# harp_behavior_v2_0.net
KiCad netlist of a schematic drawn in EAGLE
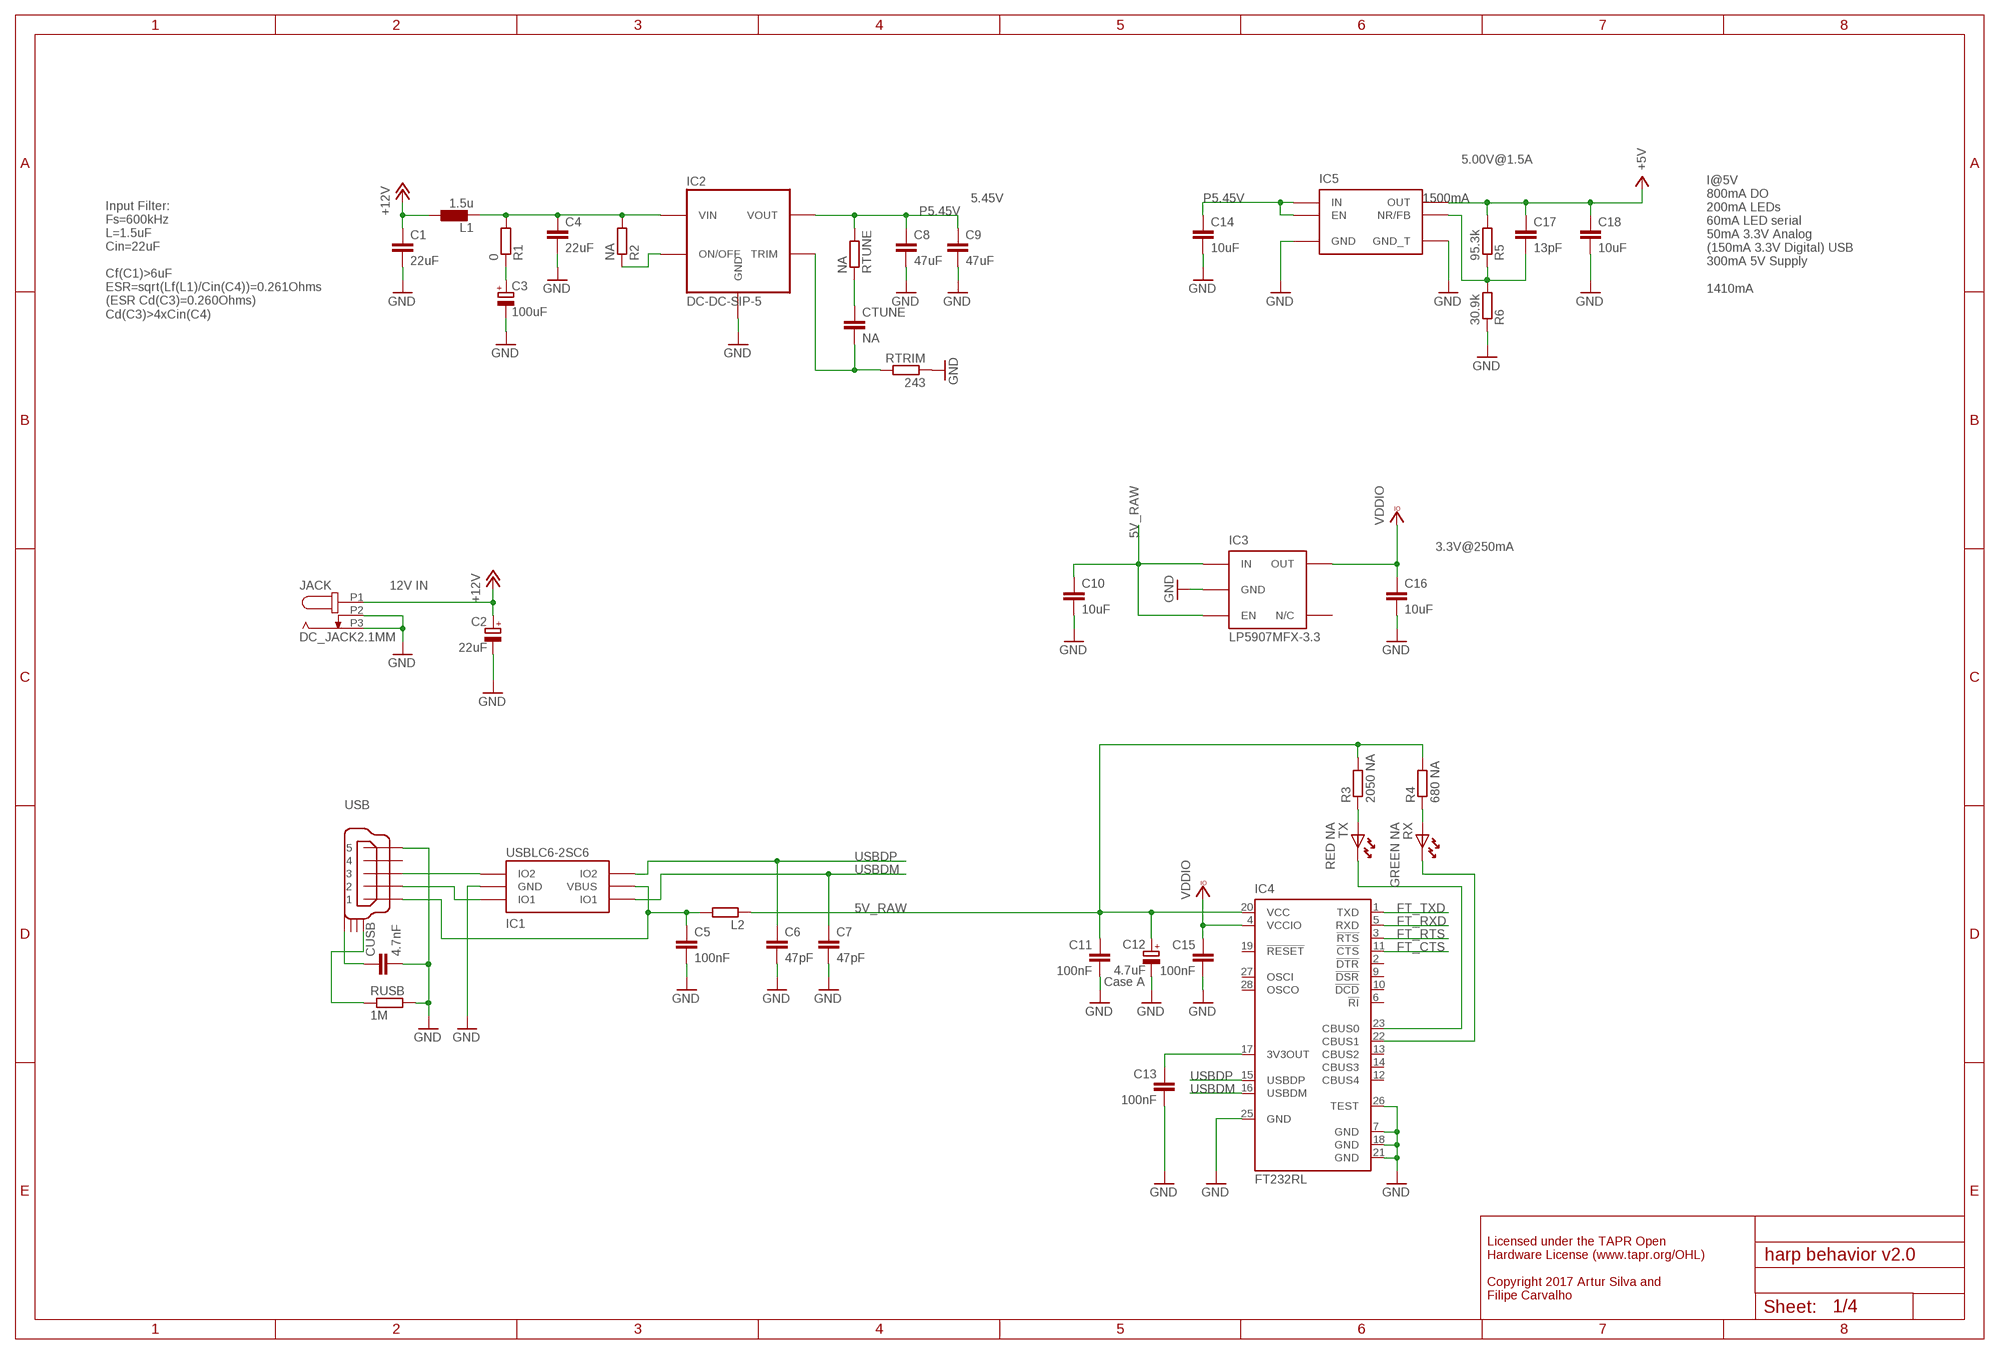
[diagram p0: schematic, sheet 1]
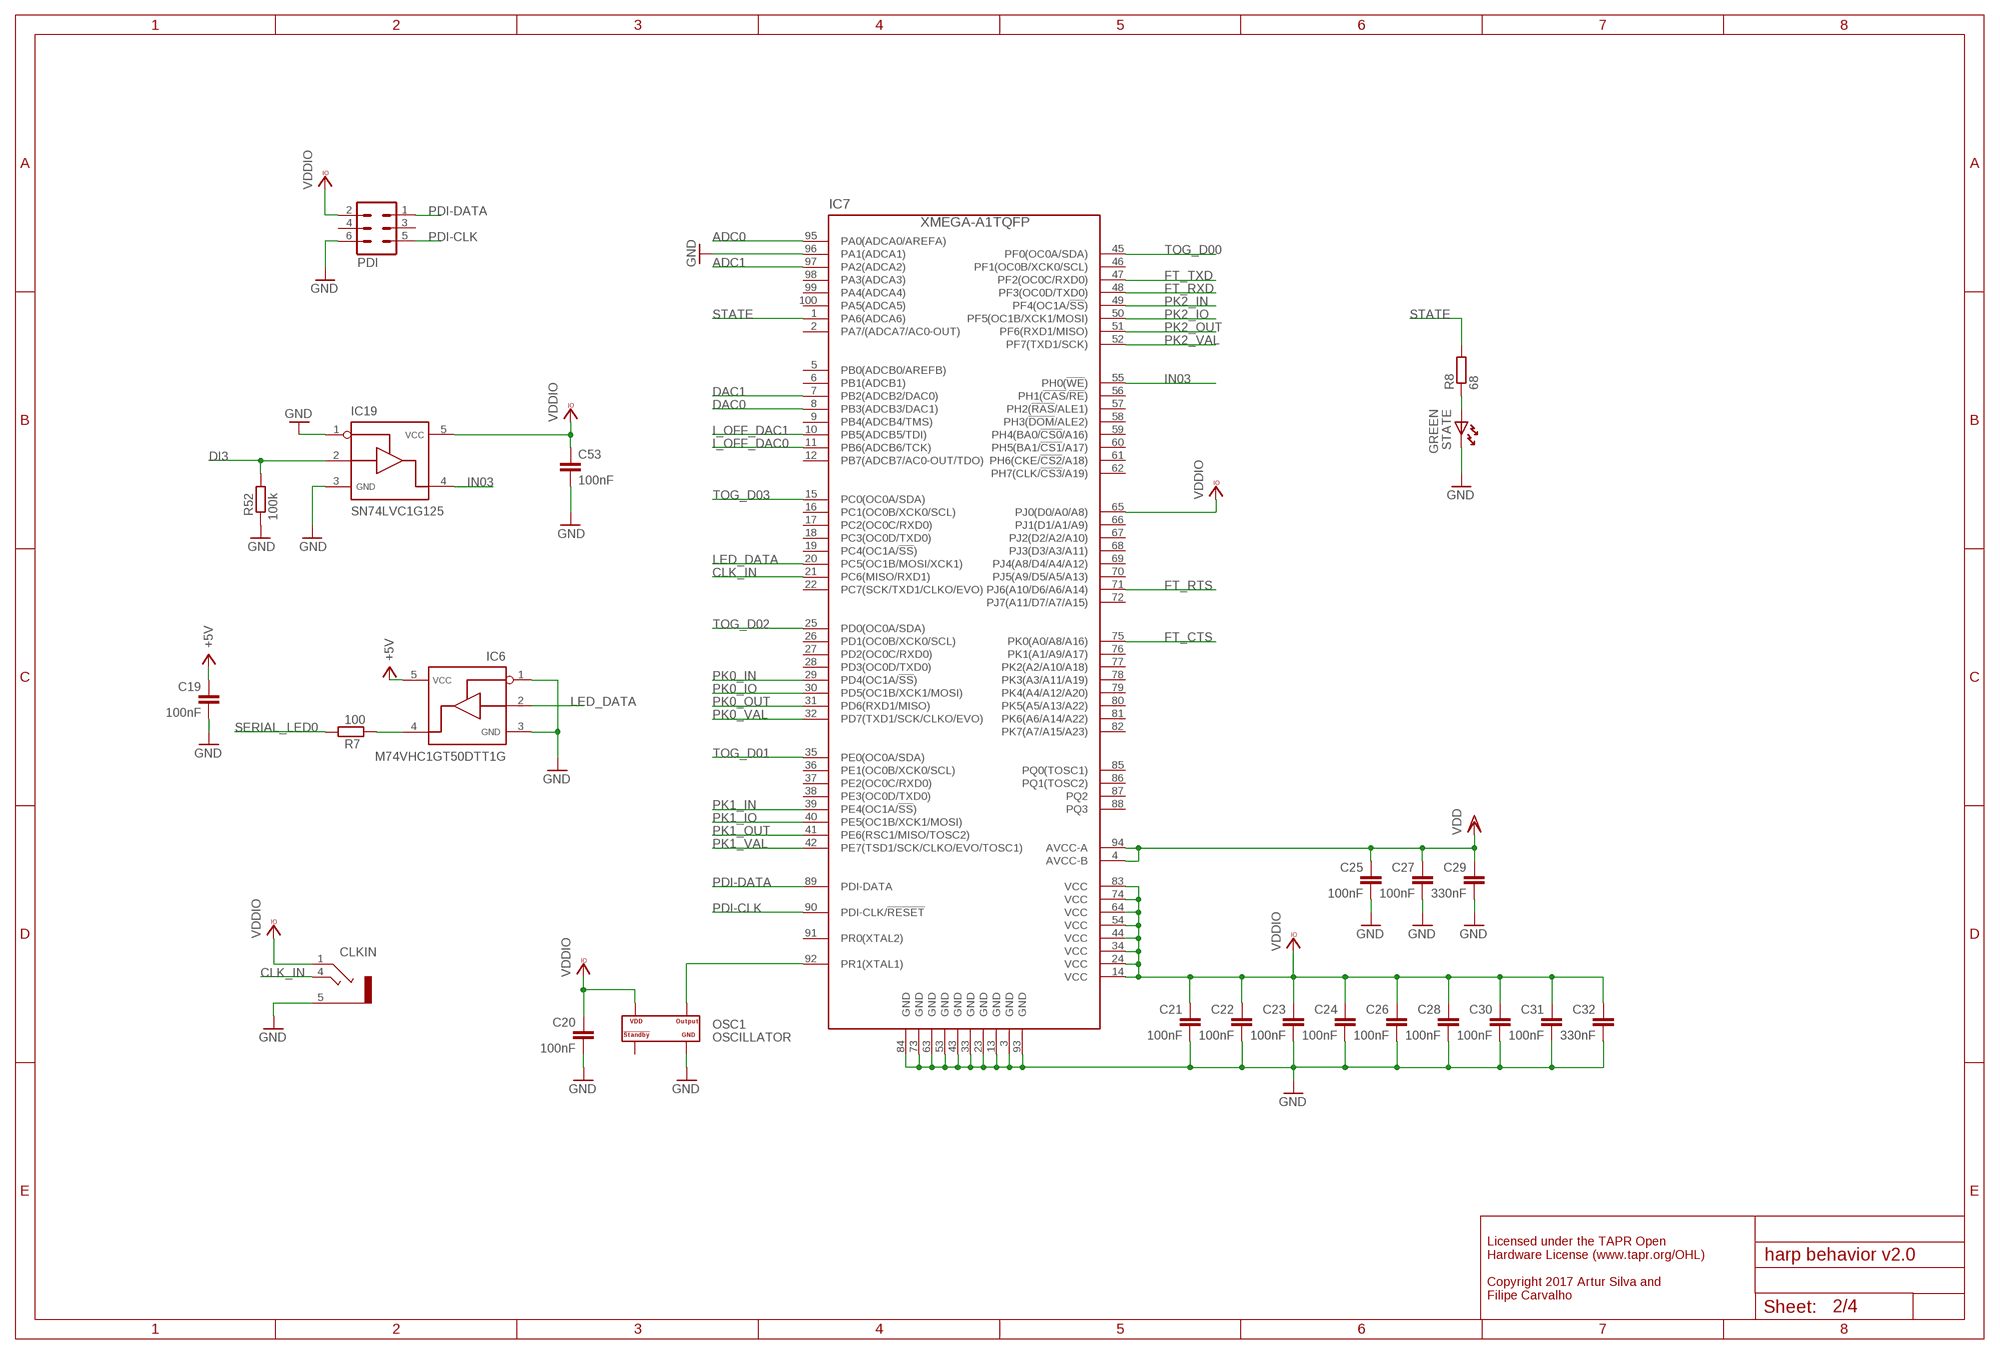
[diagram p1: schematic, sheet 2]
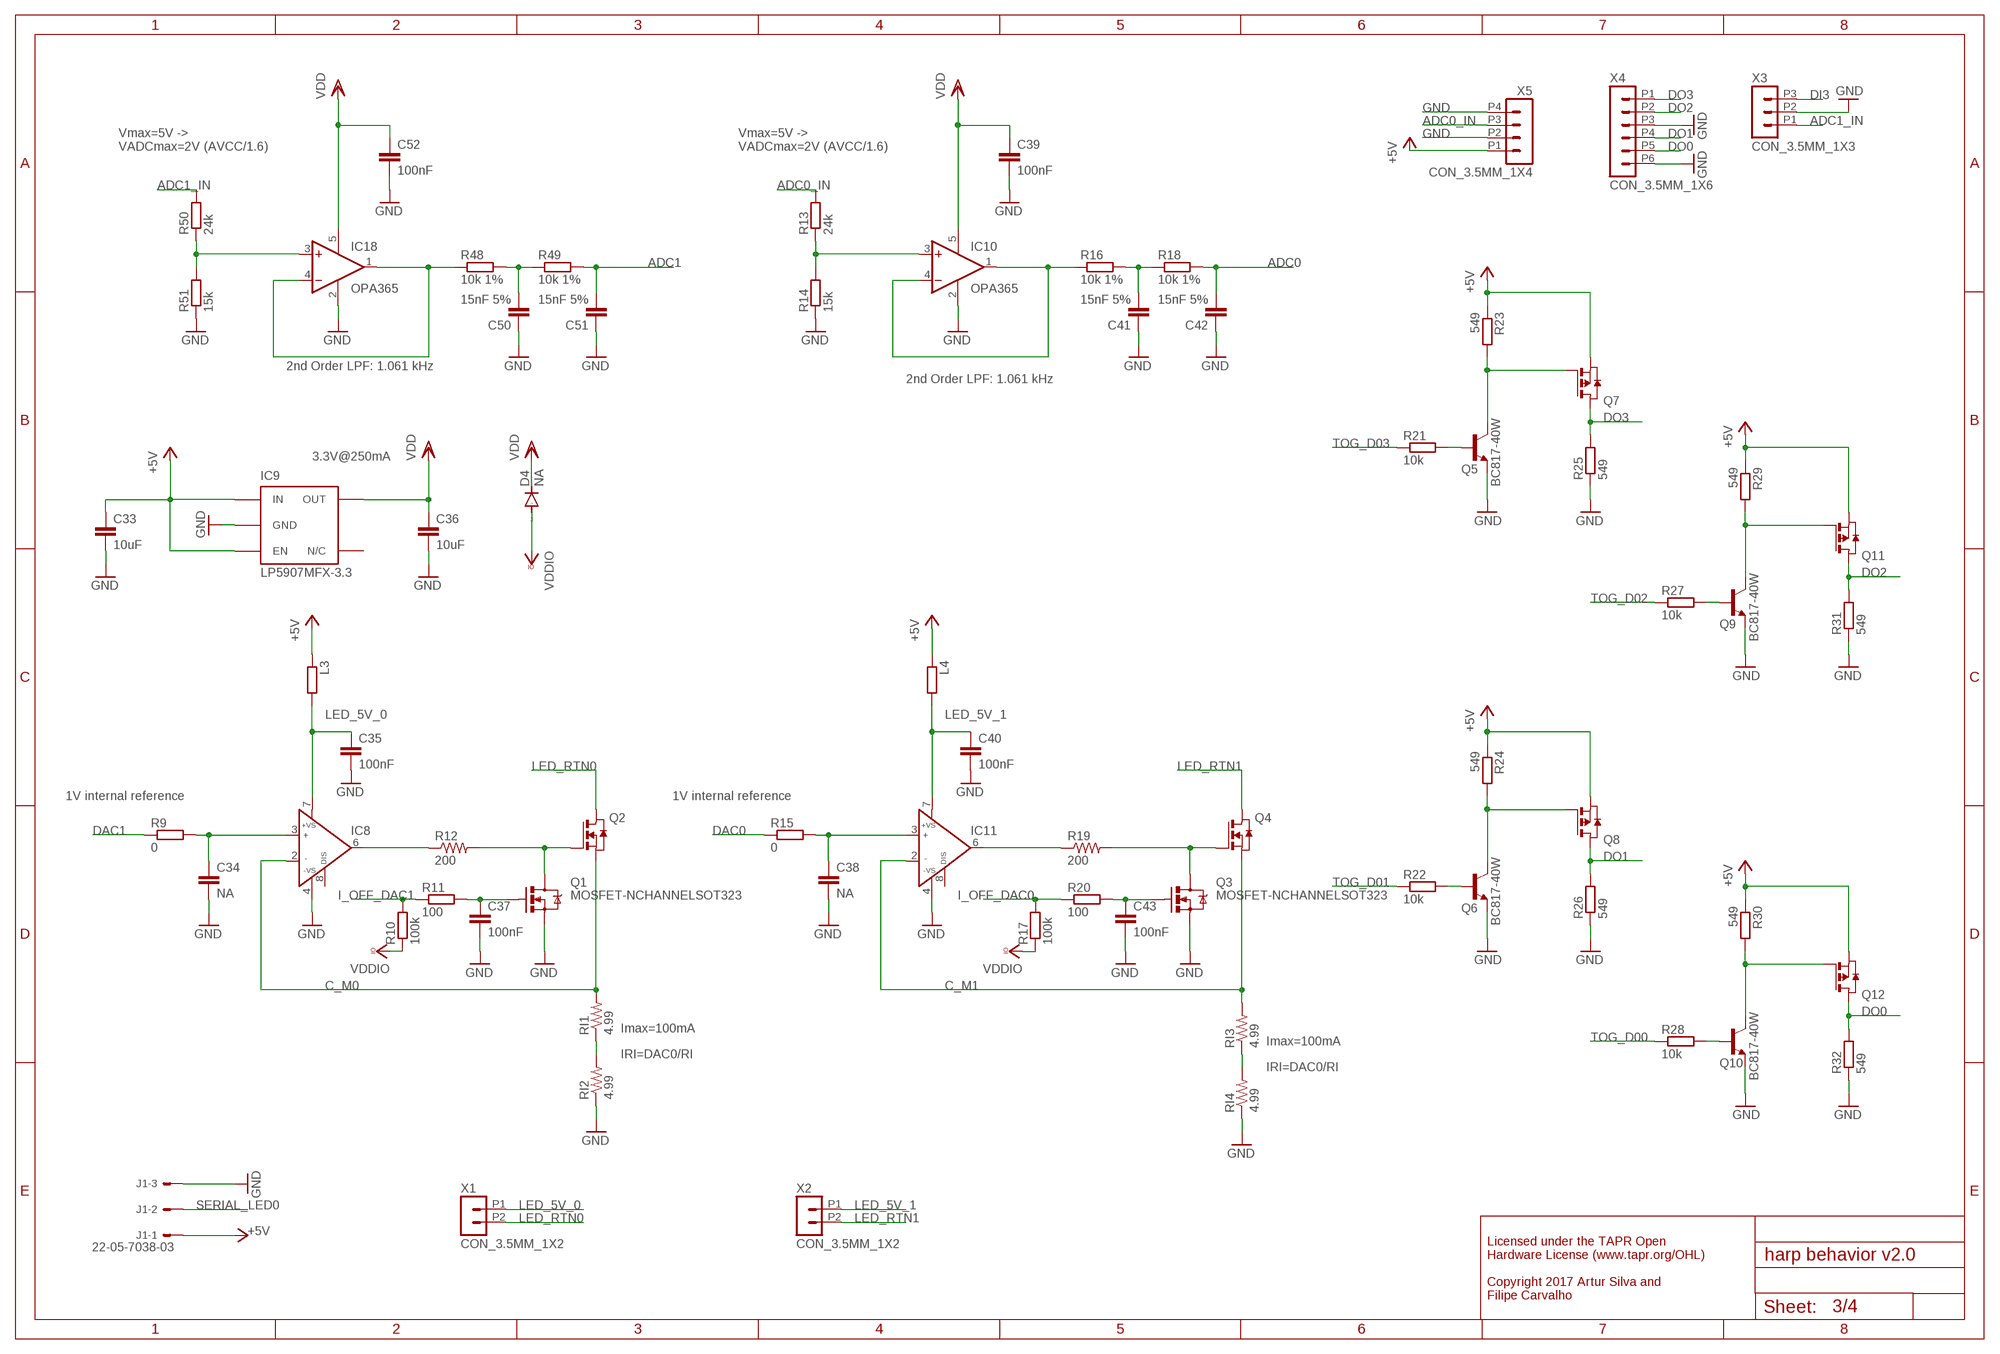
[diagram p2: schematic, sheet 3]
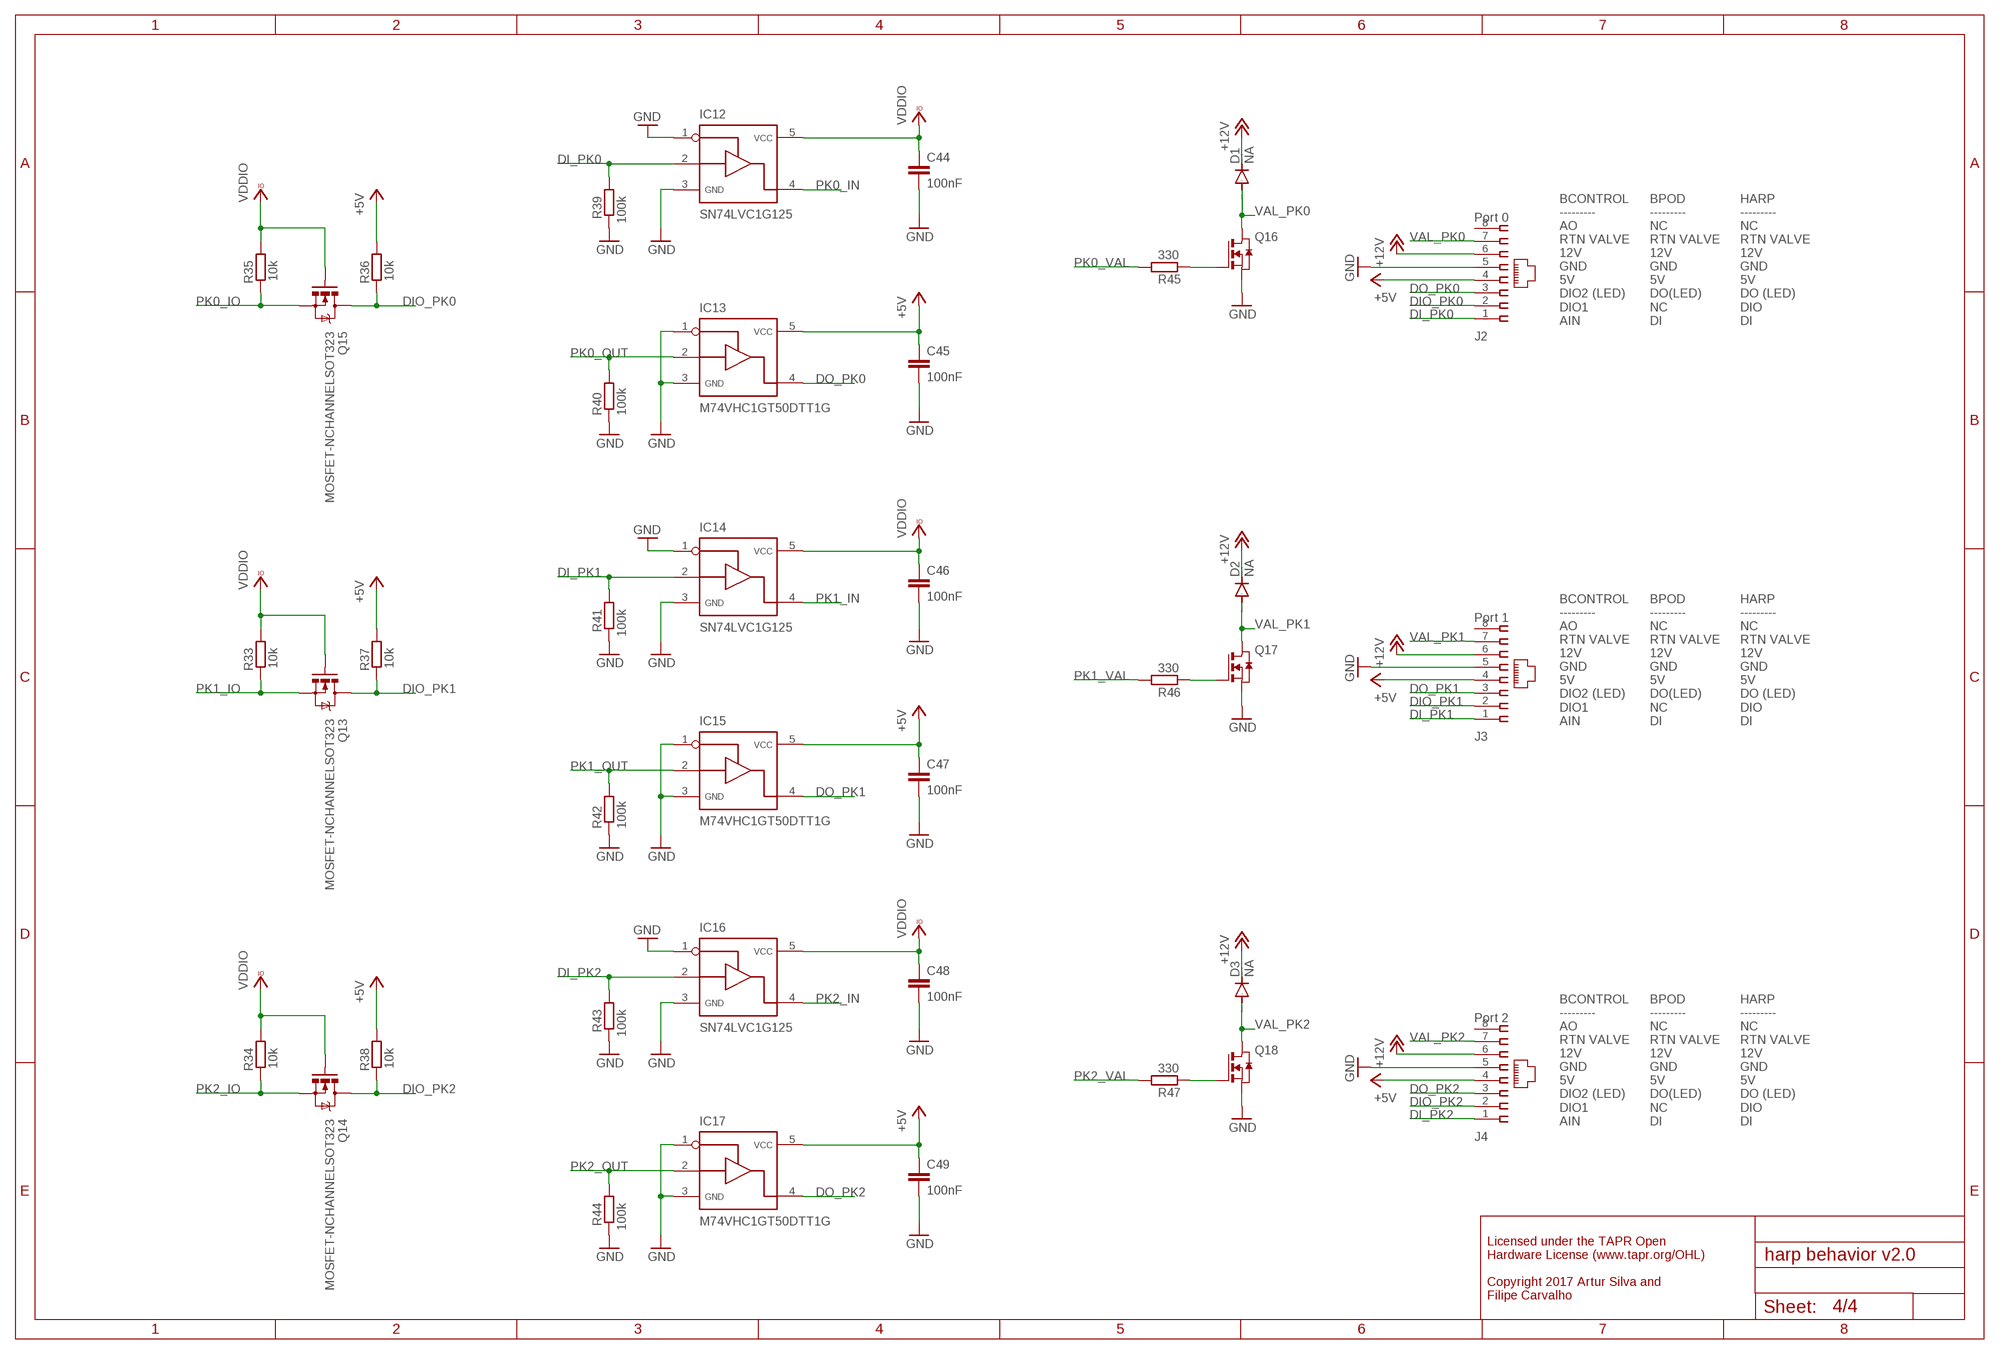
[diagram p3: schematic, sheet 4]

(export (version "E")
  (design (tool "Eeschema 10.0.6"))
  (components
    (comp (ref "C1")
      (value "22uF")
      (footprint "eagle-import:C1210")
      (libsource (lib "eagle-import") (part "C-EUC1210"))
    )
    (comp (ref "C2")
      (value "22uF")
      (footprint "eagle-import:CAP_100UF_HAND")
      (libsource (lib "eagle-import") (part "CAP_100UFHAND"))
    )
    (comp (ref "C3")
      (value "100uF")
      (footprint "eagle-import:PANASONIC_E")
      (libsource (lib "eagle-import") (part "CPOL-EUE"))
    )
    (comp (ref "C4")
      (value "22uF")
      (footprint "eagle-import:C1210")
      (libsource (lib "eagle-import") (part "C-EUC1210"))
    )
    (comp (ref "C5")
      (value "100nF")
      (footprint "eagle-import:C0402")
      (libsource (lib "eagle-import") (part "C-EUC0402"))
    )
    (comp (ref "C6")
      (value "47pF")
      (footprint "eagle-import:C0402")
      (libsource (lib "eagle-import") (part "C-EUC0402"))
    )
    (comp (ref "C7")
      (value "47pF")
      (footprint "eagle-import:C0402")
      (libsource (lib "eagle-import") (part "C-EUC0402"))
    )
    (comp (ref "C8")
      (value "47uF")
      (footprint "eagle-import:C1210")
      (libsource (lib "eagle-import") (part "C-EUC1210"))
    )
    (comp (ref "C9")
      (value "47uF")
      (footprint "eagle-import:C1210")
      (libsource (lib "eagle-import") (part "C-EUC1210"))
    )
    (comp (ref "C10")
      (value "10uF")
      (footprint "eagle-import:C0603")
      (libsource (lib "eagle-import") (part "C-EUC0603"))
    )
    (comp (ref "C11")
      (value "100nF")
      (footprint "eagle-import:C0402")
      (libsource (lib "eagle-import") (part "C-EUC0402"))
    )
    (comp (ref "C12")
      (value "4.7uF")
      (footprint "eagle-import:A_3216-18W")
      (libsource (lib "eagle-import") (part "CPOL-EUA/3216-18W"))
    )
    (comp (ref "C13")
      (value "100nF")
      (footprint "eagle-import:C0402")
      (libsource (lib "eagle-import") (part "C-EUC0402"))
    )
    (comp (ref "C14")
      (value "10uF")
      (footprint "eagle-import:C0603")
      (libsource (lib "eagle-import") (part "C-EUC0603"))
    )
    (comp (ref "C15")
      (value "100nF")
      (footprint "eagle-import:C0402")
      (libsource (lib "eagle-import") (part "C-EUC0402"))
    )
    (comp (ref "C16")
      (value "10uF")
      (footprint "eagle-import:C0603")
      (libsource (lib "eagle-import") (part "C-EUC0603"))
    )
    (comp (ref "C17")
      (value "13pF")
      (footprint "eagle-import:C0402")
      (libsource (lib "eagle-import") (part "C-EUC0402"))
    )
    (comp (ref "C18")
      (value "10uF")
      (footprint "eagle-import:C0603")
      (libsource (lib "eagle-import") (part "C-EUC0603"))
    )
    (comp (ref "CTUNE")
      (value "NA")
      (footprint "eagle-import:C0402")
      (libsource (lib "eagle-import") (part "C-EUC0402"))
    )
    (comp (ref "CUSB")
      (value "4.7nF")
      (footprint "eagle-import:C0402")
      (libsource (lib "eagle-import") (part "C-EUC0402"))
    )
    (comp (ref "IC1")
      (value "USBLC6-2SC6")
      (footprint "eagle-import:SOT23-6L")
      (libsource (lib "eagle-import") (part "USBLC6-2"))
    )
    (comp (ref "IC2")
      (value "DC-DC-SIP-5")
      (footprint "eagle-import:SIP-5")
      (libsource (lib "eagle-import") (part "DC-DC-SIP-5"))
    )
    (comp (ref "IC3")
      (value "LP5907MFX-3.3")
      (footprint "eagle-import:TSOT23-5")
      (libsource (lib "eagle-import") (part "TLV700XX"))
    )
    (comp (ref "IC4")
      (value "FT232RL")
      (footprint "eagle-import:SSOP28")
      (libsource (lib "eagle-import") (part "FT232RL"))
    )
    (comp (ref "IC5")
      (value "TPS78601SON")
      (footprint "eagle-import:SON-8")
      (libsource (lib "eagle-import") (part "TPS78601SON"))
    )
    (comp (ref "JACK")
      (value "DC_JACK2.1MM")
      (footprint "eagle-import:DC_POWER_INPUT_2.1MM")
      (libsource (lib "eagle-import") (part "DC_JACK2.1MM"))
    )
    (comp (ref "L1")
      (value "1.5u")
      (footprint "eagle-import:IND_LPS4012_V2")
      (libsource (lib "eagle-import") (part "INDLPS4012_L"))
    )
    (comp (ref "L2")
      (value "???")
      (footprint "eagle-import:R0805")
      (libsource (lib "eagle-import") (part "R-EU_R0805"))
    )
    (comp (ref "R1")
      (value "0")
      (footprint "eagle-import:R0402")
      (libsource (lib "eagle-import") (part "R-EU_R0402"))
    )
    (comp (ref "R2")
      (value "NA")
      (footprint "eagle-import:R0402")
      (libsource (lib "eagle-import") (part "R-EU_R0402"))
    )
    (comp (ref "R3")
      (value "2050 NA")
      (footprint "eagle-import:R0402")
      (libsource (lib "eagle-import") (part "R-EU_R0402"))
    )
    (comp (ref "R4")
      (value "680 NA")
      (footprint "eagle-import:R0402")
      (libsource (lib "eagle-import") (part "R-EU_R0402"))
    )
    (comp (ref "R5")
      (value "95.3k")
      (footprint "eagle-import:R0402")
      (libsource (lib "eagle-import") (part "R-EU_R0402"))
    )
    (comp (ref "R6")
      (value "30.9k")
      (footprint "eagle-import:R0402")
      (libsource (lib "eagle-import") (part "R-EU_R0402"))
    )
    (comp (ref "RTRIM")
      (value "243")
      (footprint "eagle-import:R0402")
      (libsource (lib "eagle-import") (part "R-EU_R0402"))
    )
    (comp (ref "RTUNE")
      (value "NA")
      (footprint "eagle-import:R0402")
      (libsource (lib "eagle-import") (part "R-EU_R0402"))
    )
    (comp (ref "RUSB")
      (value "1M")
      (footprint "eagle-import:R0402")
      (libsource (lib "eagle-import") (part "R-EU_R0402"))
    )
    (comp (ref "RX")
      (value "GREEN NA")
      (footprint "eagle-import:LED_HAND")
      (libsource (lib "eagle-import") (part "LEDHAND"))
    )
    (comp (ref "TX")
      (value "RED NA")
      (footprint "eagle-import:LED_HAND")
      (libsource (lib "eagle-import") (part "LEDHAND"))
    )
    (comp (ref "USB")
      (value "USB_MINI_B")
      (footprint "eagle-import:240-0002-1")
      (libsource (lib "eagle-import") (part "USB_MINI_B"))
    )
    (comp (ref "C44")
      (value "100nF")
      (footprint "eagle-import:C0402")
      (libsource (lib "eagle-import") (part "C-EUC0402"))
    )
    (comp (ref "C45")
      (value "100nF")
      (footprint "eagle-import:C0402")
      (libsource (lib "eagle-import") (part "C-EUC0402"))
    )
    (comp (ref "C46")
      (value "100nF")
      (footprint "eagle-import:C0402")
      (libsource (lib "eagle-import") (part "C-EUC0402"))
    )
    (comp (ref "C47")
      (value "100nF")
      (footprint "eagle-import:C0402")
      (libsource (lib "eagle-import") (part "C-EUC0402"))
    )
    (comp (ref "C48")
      (value "100nF")
      (footprint "eagle-import:C0402")
      (libsource (lib "eagle-import") (part "C-EUC0402"))
    )
    (comp (ref "C49")
      (value "100nF")
      (footprint "eagle-import:C0402")
      (libsource (lib "eagle-import") (part "C-EUC0402"))
    )
    (comp (ref "D1")
      (value "NA")
      (footprint "eagle-import:SOD-323-DIODE")
      (libsource (lib "eagle-import") (part "DIODE"))
    )
    (comp (ref "D2")
      (value "NA")
      (footprint "eagle-import:SOD-323-DIODE")
      (libsource (lib "eagle-import") (part "DIODE"))
    )
    (comp (ref "D3")
      (value "NA")
      (footprint "eagle-import:SOD-323-DIODE")
      (libsource (lib "eagle-import") (part "DIODE"))
    )
    (comp (ref "IC12")
      (value "SN74LVC1G125")
      (footprint "eagle-import:SOT23-5")
      (libsource (lib "eagle-import") (part "SN74LVC1G125"))
    )
    (comp (ref "IC13")
      (value "M74VHC1GT50DTT1G")
      (footprint "eagle-import:SOT23-5")
      (libsource (lib "eagle-import") (part "SN74LVC1G125"))
    )
    (comp (ref "IC14")
      (value "SN74LVC1G125")
      (footprint "eagle-import:SOT23-5")
      (libsource (lib "eagle-import") (part "SN74LVC1G125"))
    )
    (comp (ref "IC15")
      (value "M74VHC1GT50DTT1G")
      (footprint "eagle-import:SOT23-5")
      (libsource (lib "eagle-import") (part "SN74LVC1G125"))
    )
    (comp (ref "IC16")
      (value "SN74LVC1G125")
      (footprint "eagle-import:SOT23-5")
      (libsource (lib "eagle-import") (part "SN74LVC1G125"))
    )
    (comp (ref "IC17")
      (value "M74VHC1GT50DTT1G")
      (footprint "eagle-import:SOT23-5")
      (libsource (lib "eagle-import") (part "SN74LVC1G125"))
    )
    (comp (ref "J2")
      (value "Port 0")
      (footprint "eagle-import:520426-4")
      (libsource (lib "eagle-import") (part "520426-4"))
    )
    (comp (ref "J3")
      (value "Port 1")
      (footprint "eagle-import:520426-4")
      (libsource (lib "eagle-import") (part "520426-4"))
    )
    (comp (ref "J4")
      (value "Port 2")
      (footprint "eagle-import:520426-4")
      (libsource (lib "eagle-import") (part "520426-4"))
    )
    (comp (ref "Q13")
      (value "MOSFET-NCHANNELSOT323")
      (footprint "eagle-import:SOT323")
      (libsource (lib "eagle-import") (part "MOSFET-NCHANNELSOT323"))
    )
    (comp (ref "Q14")
      (value "MOSFET-NCHANNELSOT323")
      (footprint "eagle-import:SOT323")
      (libsource (lib "eagle-import") (part "MOSFET-NCHANNELSOT323"))
    )
    (comp (ref "Q15")
      (value "MOSFET-NCHANNELSOT323")
      (footprint "eagle-import:SOT323")
      (libsource (lib "eagle-import") (part "MOSFET-NCHANNELSOT323"))
    )
    (comp (ref "Q16")
      (value "NMOSSOT223")
      (footprint "eagle-import:SOT223")
      (libsource (lib "eagle-import") (part "NMOSSOT223"))
    )
    (comp (ref "Q17")
      (value "NMOSSOT223")
      (footprint "eagle-import:SOT223")
      (libsource (lib "eagle-import") (part "NMOSSOT223"))
    )
    (comp (ref "Q18")
      (value "NMOSSOT223")
      (footprint "eagle-import:SOT223")
      (libsource (lib "eagle-import") (part "NMOSSOT223"))
    )
    (comp (ref "R33")
      (value "10k")
      (footprint "eagle-import:R0402")
      (libsource (lib "eagle-import") (part "R-EU_R0402"))
    )
    (comp (ref "R34")
      (value "10k")
      (footprint "eagle-import:R0402")
      (libsource (lib "eagle-import") (part "R-EU_R0402"))
    )
    (comp (ref "R35")
      (value "10k")
      (footprint "eagle-import:R0402")
      (libsource (lib "eagle-import") (part "R-EU_R0402"))
    )
    (comp (ref "R36")
      (value "10k")
      (footprint "eagle-import:R0402")
      (libsource (lib "eagle-import") (part "R-EU_R0402"))
    )
    (comp (ref "R37")
      (value "10k")
      (footprint "eagle-import:R0402")
      (libsource (lib "eagle-import") (part "R-EU_R0402"))
    )
    (comp (ref "R38")
      (value "10k")
      (footprint "eagle-import:R0402")
      (libsource (lib "eagle-import") (part "R-EU_R0402"))
    )
    (comp (ref "R39")
      (value "100k")
      (footprint "eagle-import:R0402")
      (libsource (lib "eagle-import") (part "R-EU_R0402"))
    )
    (comp (ref "R40")
      (value "100k")
      (footprint "eagle-import:R0402")
      (libsource (lib "eagle-import") (part "R-EU_R0402"))
    )
    (comp (ref "R41")
      (value "100k")
      (footprint "eagle-import:R0402")
      (libsource (lib "eagle-import") (part "R-EU_R0402"))
    )
    (comp (ref "R42")
      (value "100k")
      (footprint "eagle-import:R0402")
      (libsource (lib "eagle-import") (part "R-EU_R0402"))
    )
    (comp (ref "R43")
      (value "100k")
      (footprint "eagle-import:R0402")
      (libsource (lib "eagle-import") (part "R-EU_R0402"))
    )
    (comp (ref "R44")
      (value "100k")
      (footprint "eagle-import:R0402")
      (libsource (lib "eagle-import") (part "R-EU_R0402"))
    )
    (comp (ref "R45")
      (value "330")
      (footprint "eagle-import:R0402")
      (libsource (lib "eagle-import") (part "R-EU_R0402"))
    )
    (comp (ref "R46")
      (value "330")
      (footprint "eagle-import:R0402")
      (libsource (lib "eagle-import") (part "R-EU_R0402"))
    )
    (comp (ref "R47")
      (value "330")
      (footprint "eagle-import:R0402")
      (libsource (lib "eagle-import") (part "R-EU_R0402"))
    )
    (comp (ref "C19")
      (value "100nF")
      (footprint "eagle-import:C0402")
      (libsource (lib "eagle-import") (part "C-EUC0402"))
    )
    (comp (ref "C20")
      (value "100nF")
      (footprint "eagle-import:C0402")
      (libsource (lib "eagle-import") (part "C-EUC0402"))
    )
    (comp (ref "C21")
      (value "100nF")
      (footprint "eagle-import:C0402")
      (libsource (lib "eagle-import") (part "C-EUC0402"))
    )
    (comp (ref "C22")
      (value "100nF")
      (footprint "eagle-import:C0402")
      (libsource (lib "eagle-import") (part "C-EUC0402"))
    )
    (comp (ref "C23")
      (value "100nF")
      (footprint "eagle-import:C0402")
      (libsource (lib "eagle-import") (part "C-EUC0402"))
    )
    (comp (ref "C24")
      (value "100nF")
      (footprint "eagle-import:C0402")
      (libsource (lib "eagle-import") (part "C-EUC0402"))
    )
    (comp (ref "C25")
      (value "100nF")
      (footprint "eagle-import:C0402")
      (libsource (lib "eagle-import") (part "C-EUC0402"))
    )
    (comp (ref "C26")
      (value "100nF")
      (footprint "eagle-import:C0402")
      (libsource (lib "eagle-import") (part "C-EUC0402"))
    )
    (comp (ref "C27")
      (value "100nF")
      (footprint "eagle-import:C0402")
      (libsource (lib "eagle-import") (part "C-EUC0402"))
    )
    (comp (ref "C28")
      (value "100nF")
      (footprint "eagle-import:C0402")
      (libsource (lib "eagle-import") (part "C-EUC0402"))
    )
    (comp (ref "C29")
      (value "330nF")
      (footprint "eagle-import:C0402")
      (libsource (lib "eagle-import") (part "C-EUC0402"))
    )
    (comp (ref "C30")
      (value "100nF")
      (footprint "eagle-import:C0402")
      (libsource (lib "eagle-import") (part "C-EUC0402"))
    )
    (comp (ref "C31")
      (value "100nF")
      (footprint "eagle-import:C0402")
      (libsource (lib "eagle-import") (part "C-EUC0402"))
    )
    (comp (ref "C32")
      (value "330nF")
      (footprint "eagle-import:C0402")
      (libsource (lib "eagle-import") (part "C-EUC0402"))
    )
    (comp (ref "C53")
      (value "100nF")
      (footprint "eagle-import:C0402")
      (libsource (lib "eagle-import") (part "C-EUC0402"))
    )
    (comp (ref "CLKIN")
      (value "STEREO_JACK")
      (footprint "eagle-import:35RASMT2BHNTRX")
      (libsource (lib "eagle-import") (part "STEREO_JACK"))
    )
    (comp (ref "IC6")
      (value "M74VHC1GT50DTT1G")
      (footprint "eagle-import:SOT23-5")
      (libsource (lib "eagle-import") (part "SN74LVC1G125"))
    )
    (comp (ref "IC7")
      (value "XMEGA-A1TQFP")
      (footprint "eagle-import:TQFP100")
      (libsource (lib "eagle-import") (part "XMEGA-A1TQFP"))
    )
    (comp (ref "IC19")
      (value "SN74LVC1G125")
      (footprint "eagle-import:SOT23-5")
      (libsource (lib "eagle-import") (part "SN74LVC1G125"))
    )
    (comp (ref "OSC1")
      (value "OSCILLATOR")
      (footprint "eagle-import:OSCILLATOR_3.2X2.5")
      (libsource (lib "eagle-import") (part "OSCILLATOR"))
    )
    (comp (ref "PDI")
      (value "MA03-2")
      (footprint "eagle-import:MA03-2")
      (libsource (lib "eagle-import") (part "MA03-2"))
    )
    (comp (ref "R7")
      (value "100")
      (footprint "eagle-import:R0402")
      (libsource (lib "eagle-import") (part "R-EU_R0402"))
    )
    (comp (ref "R8")
      (value "68")
      (footprint "eagle-import:R0402")
      (libsource (lib "eagle-import") (part "R-EU_R0402"))
    )
    (comp (ref "R52")
      (value "100k")
      (footprint "eagle-import:R0402")
      (libsource (lib "eagle-import") (part "R-EU_R0402"))
    )
    (comp (ref "STATE")
      (value "GREEN")
      (footprint "eagle-import:LED_HAND")
      (libsource (lib "eagle-import") (part "LEDHAND"))
    )
    (comp (ref "C33")
      (value "10uF")
      (footprint "eagle-import:C0603")
      (libsource (lib "eagle-import") (part "C-EUC0603"))
    )
    (comp (ref "C34")
      (value "NA")
      (footprint "eagle-import:C0402")
      (libsource (lib "eagle-import") (part "C-EUC0402"))
    )
    (comp (ref "C35")
      (value "100nF")
      (footprint "eagle-import:C0402")
      (libsource (lib "eagle-import") (part "C-EUC0402"))
    )
    (comp (ref "C36")
      (value "10uF")
      (footprint "eagle-import:C0603")
      (libsource (lib "eagle-import") (part "C-EUC0603"))
    )
    (comp (ref "C37")
      (value "100nF")
      (footprint "eagle-import:C0402")
      (libsource (lib "eagle-import") (part "C-EUC0402"))
    )
    (comp (ref "C38")
      (value "NA")
      (footprint "eagle-import:C0402")
      (libsource (lib "eagle-import") (part "C-EUC0402"))
    )
    (comp (ref "C39")
      (value "100nF")
      (footprint "eagle-import:C0402")
      (libsource (lib "eagle-import") (part "C-EUC0402"))
    )
    (comp (ref "C40")
      (value "100nF")
      (footprint "eagle-import:C0402")
      (libsource (lib "eagle-import") (part "C-EUC0402"))
    )
    (comp (ref "C41")
      (value "15nF 5%")
      (footprint "eagle-import:C0402")
      (libsource (lib "eagle-import") (part "C-EUC0402"))
    )
    (comp (ref "C42")
      (value "15nF 5%")
      (footprint "eagle-import:C0402")
      (libsource (lib "eagle-import") (part "C-EUC0402"))
    )
    (comp (ref "C43")
      (value "100nF")
      (footprint "eagle-import:C0402")
      (libsource (lib "eagle-import") (part "C-EUC0402"))
    )
    (comp (ref "C50")
      (value "15nF 5%")
      (footprint "eagle-import:C0402")
      (libsource (lib "eagle-import") (part "C-EUC0402"))
    )
    (comp (ref "C51")
      (value "15nF 5%")
      (footprint "eagle-import:C0402")
      (libsource (lib "eagle-import") (part "C-EUC0402"))
    )
    (comp (ref "C52")
      (value "100nF")
      (footprint "eagle-import:C0402")
      (libsource (lib "eagle-import") (part "C-EUC0402"))
    )
    (comp (ref "D4")
      (value "NA")
      (footprint "eagle-import:SOD-323-DIODE")
      (libsource (lib "eagle-import") (part "DIODE"))
    )
    (comp (ref "IC8")
      (value "AD8041R")
      (footprint "eagle-import:SO8")
      (fields (field (name "MF") "ALTERA CORPORATION") (field (name "MPN") "AD8041ARZ"))
      (libsource (lib "eagle-import") (part "AD8041R"))
    )
    (comp (ref "IC9")
      (value "LP5907MFX-3.3")
      (footprint "eagle-import:TSOT23-5")
      (libsource (lib "eagle-import") (part "TLV700XX"))
    )
    (comp (ref "IC10")
      (value "OPA365")
      (footprint "eagle-import:SOT23-5")
      (libsource (lib "eagle-import") (part "OPA365"))
    )
    (comp (ref "IC11")
      (value "AD8041R")
      (footprint "eagle-import:SO8")
      (fields (field (name "MF") "ALTERA CORPORATION") (field (name "MPN") "AD8041ARZ"))
      (libsource (lib "eagle-import") (part "AD8041R"))
    )
    (comp (ref "IC18")
      (value "OPA365")
      (footprint "eagle-import:SOT23-5")
      (libsource (lib "eagle-import") (part "OPA365"))
    )
    (comp (ref "J1")
      (value "22-05-7038-03")
      (footprint "eagle-import:7395-03")
      (libsource (lib "eagle-import") (part "22-?-0305-7038"))
    )
    (comp (ref "L3")
      (value "600@100M")
      (footprint "eagle-import:R0805")
      (libsource (lib "eagle-import") (part "R-EU_R0805"))
    )
    (comp (ref "L4")
      (value "600@100M")
      (footprint "eagle-import:R0805")
      (libsource (lib "eagle-import") (part "R-EU_R0805"))
    )
    (comp (ref "Q1")
      (value "MOSFET-NCHANNELSOT323")
      (footprint "eagle-import:SOT323")
      (libsource (lib "eagle-import") (part "MOSFET-NCHANNELSOT323"))
    )
    (comp (ref "Q2")
      (value "NMOSSOT223")
      (footprint "eagle-import:SOT223")
      (libsource (lib "eagle-import") (part "NMOSSOT223"))
    )
    (comp (ref "Q3")
      (value "MOSFET-NCHANNELSOT323")
      (footprint "eagle-import:SOT323")
      (libsource (lib "eagle-import") (part "MOSFET-NCHANNELSOT323"))
    )
    (comp (ref "Q4")
      (value "NMOSSOT223")
      (footprint "eagle-import:SOT223")
      (libsource (lib "eagle-import") (part "NMOSSOT223"))
    )
    (comp (ref "Q5")
      (value "BC817-40W")
      (footprint "eagle-import:SOT323-BEC")
      (libsource (lib "eagle-import") (part "BC817"))
    )
    (comp (ref "Q6")
      (value "BC817-40W")
      (footprint "eagle-import:SOT323-BEC")
      (libsource (lib "eagle-import") (part "BC817"))
    )
    (comp (ref "Q7")
      (value "PMOSSOT223")
      (footprint "eagle-import:SOT223")
      (libsource (lib "eagle-import") (part "PMOSSOT223"))
    )
    (comp (ref "Q8")
      (value "PMOSSOT223")
      (footprint "eagle-import:SOT223")
      (libsource (lib "eagle-import") (part "PMOSSOT223"))
    )
    (comp (ref "Q9")
      (value "BC817-40W")
      (footprint "eagle-import:SOT323-BEC")
      (libsource (lib "eagle-import") (part "BC817"))
    )
    (comp (ref "Q10")
      (value "BC817-40W")
      (footprint "eagle-import:SOT323-BEC")
      (libsource (lib "eagle-import") (part "BC817"))
    )
    (comp (ref "Q11")
      (value "PMOSSOT223")
      (footprint "eagle-import:SOT223")
      (libsource (lib "eagle-import") (part "PMOSSOT223"))
    )
    (comp (ref "Q12")
      (value "PMOSSOT223")
      (footprint "eagle-import:SOT223")
      (libsource (lib "eagle-import") (part "PMOSSOT223"))
    )
    (comp (ref "R9")
      (value "0")
      (footprint "eagle-import:R0402")
      (libsource (lib "eagle-import") (part "R-EU_R0402"))
    )
    (comp (ref "R10")
      (value "100k")
      (footprint "eagle-import:R0402")
      (libsource (lib "eagle-import") (part "R-EU_R0402"))
    )
    (comp (ref "R11")
      (value "100")
      (footprint "eagle-import:R0402")
      (libsource (lib "eagle-import") (part "R-EU_R0402"))
    )
    (comp (ref "R12")
      (value "200")
      (footprint "eagle-import:R1210")
      (libsource (lib "eagle-import") (part "R-US_R1210"))
    )
    (comp (ref "R13")
      (value "24k")
      (footprint "eagle-import:R0402")
      (libsource (lib "eagle-import") (part "R-EU_R0402"))
    )
    (comp (ref "R14")
      (value "15k")
      (footprint "eagle-import:R0402")
      (libsource (lib "eagle-import") (part "R-EU_R0402"))
    )
    (comp (ref "R15")
      (value "0")
      (footprint "eagle-import:R0402")
      (libsource (lib "eagle-import") (part "R-EU_R0402"))
    )
    (comp (ref "R16")
      (value "10k 1%")
      (footprint "eagle-import:R0402")
      (libsource (lib "eagle-import") (part "R-EU_R0402"))
    )
    (comp (ref "R17")
      (value "100k")
      (footprint "eagle-import:R0402")
      (libsource (lib "eagle-import") (part "R-EU_R0402"))
    )
    (comp (ref "R18")
      (value "10k 1%")
      (footprint "eagle-import:R0402")
      (libsource (lib "eagle-import") (part "R-EU_R0402"))
    )
    (comp (ref "R19")
      (value "200")
      (footprint "eagle-import:R1210")
      (libsource (lib "eagle-import") (part "R-US_R1210"))
    )
    (comp (ref "R20")
      (value "100")
      (footprint "eagle-import:R0402")
      (libsource (lib "eagle-import") (part "R-EU_R0402"))
    )
    (comp (ref "R21")
      (value "10k")
      (footprint "eagle-import:R0402")
      (libsource (lib "eagle-import") (part "R-EU_R0402"))
    )
    (comp (ref "R22")
      (value "10k")
      (footprint "eagle-import:R0402")
      (libsource (lib "eagle-import") (part "R-EU_R0402"))
    )
    (comp (ref "R23")
      (value "549")
      (footprint "eagle-import:R0805")
      (libsource (lib "eagle-import") (part "R-EU_R0805"))
    )
    (comp (ref "R24")
      (value "549")
      (footprint "eagle-import:R0805")
      (libsource (lib "eagle-import") (part "R-EU_R0805"))
    )
    (comp (ref "R25")
      (value "549")
      (footprint "eagle-import:R0805")
      (libsource (lib "eagle-import") (part "R-EU_R0805"))
    )
    (comp (ref "R26")
      (value "549")
      (footprint "eagle-import:R0805")
      (libsource (lib "eagle-import") (part "R-EU_R0805"))
    )
    (comp (ref "R27")
      (value "10k")
      (footprint "eagle-import:R0402")
      (libsource (lib "eagle-import") (part "R-EU_R0402"))
    )
    (comp (ref "R28")
      (value "10k")
      (footprint "eagle-import:R0402")
      (libsource (lib "eagle-import") (part "R-EU_R0402"))
    )
    (comp (ref "R29")
      (value "549")
      (footprint "eagle-import:R0805")
      (libsource (lib "eagle-import") (part "R-EU_R0805"))
    )
    (comp (ref "R30")
      (value "549")
      (footprint "eagle-import:R0805")
      (libsource (lib "eagle-import") (part "R-EU_R0805"))
    )
    (comp (ref "R31")
      (value "549")
      (footprint "eagle-import:R0805")
      (libsource (lib "eagle-import") (part "R-EU_R0805"))
    )
    (comp (ref "R32")
      (value "549")
      (footprint "eagle-import:R0805")
      (libsource (lib "eagle-import") (part "R-EU_R0805"))
    )
    (comp (ref "R48")
      (value "10k 1%")
      (footprint "eagle-import:R0402")
      (libsource (lib "eagle-import") (part "R-EU_R0402"))
    )
    (comp (ref "R49")
      (value "10k 1%")
      (footprint "eagle-import:R0402")
      (libsource (lib "eagle-import") (part "R-EU_R0402"))
    )
    (comp (ref "R50")
      (value "24k")
      (footprint "eagle-import:R0402")
      (libsource (lib "eagle-import") (part "R-EU_R0402"))
    )
    (comp (ref "R51")
      (value "15k")
      (footprint "eagle-import:R0402")
      (libsource (lib "eagle-import") (part "R-EU_R0402"))
    )
    (comp (ref "RI1")
      (value "4.99")
      (footprint "eagle-import:R2512")
      (libsource (lib "eagle-import") (part "R-US_R2512"))
    )
    (comp (ref "RI2")
      (value "4.99")
      (footprint "eagle-import:R2512")
      (libsource (lib "eagle-import") (part "R-US_R2512"))
    )
    (comp (ref "RI3")
      (value "4.99")
      (footprint "eagle-import:R2512")
      (libsource (lib "eagle-import") (part "R-US_R2512"))
    )
    (comp (ref "RI4")
      (value "4.99")
      (footprint "eagle-import:R2512")
      (libsource (lib "eagle-import") (part "R-US_R2512"))
    )
    (comp (ref "X1")
      (value "CON_3.5MM_1X2")
      (footprint "eagle-import:CON_3.5MM_1X2")
      (libsource (lib "eagle-import") (part "CON_3.5MM_1X2"))
    )
    (comp (ref "X2")
      (value "CON_3.5MM_1X2")
      (footprint "eagle-import:CON_3.5MM_1X2")
      (libsource (lib "eagle-import") (part "CON_3.5MM_1X2"))
    )
    (comp (ref "X3")
      (value "CON_3.5MM_1X3")
      (footprint "eagle-import:CON_3.5MM_1X3")
      (libsource (lib "eagle-import") (part "CON_3.5MM_1X3"))
    )
    (comp (ref "X4")
      (value "CON_3.5MM_1X6")
      (footprint "eagle-import:CON_3.5MM_1X6")
      (libsource (lib "eagle-import") (part "CON_3.5MM_1X6"))
    )
    (comp (ref "X5")
      (value "CON_3.5MM_1X4")
      (footprint "eagle-import:CON_3.5MM_1X4")
      (libsource (lib "eagle-import") (part "CON_3.5MM_1X4"))
    )
  )
  (nets
    (net (code "1") (name "+5V") (class "Default")
      (node (ref "C17") (pin "1") (pinfunction "1_1") (pintype "passive"))
      (node (ref "C18") (pin "1") (pinfunction "1_1") (pintype "passive"))
      (node (ref "C19") (pin "1") (pinfunction "1_1") (pintype "passive"))
      (node (ref "C33") (pin "1") (pinfunction "1_1") (pintype "passive"))
      (node (ref "C45") (pin "1") (pinfunction "1_1") (pintype "passive"))
      (node (ref "C47") (pin "1") (pinfunction "1_1") (pintype "passive"))
      (node (ref "C49") (pin "1") (pinfunction "1_1") (pintype "passive"))
      (node (ref "IC13") (pin "5") (pinfunction "P$5_5") (pintype "bidirectional"))
      (node (ref "IC15") (pin "5") (pinfunction "P$5_5") (pintype "bidirectional"))
      (node (ref "IC17") (pin "5") (pinfunction "P$5_5") (pintype "bidirectional"))
      (node (ref "IC5") (pin "P3") (pinfunction "OUT_P3") (pintype "bidirectional"))
      (node (ref "IC5") (pin "P4") (pinfunction "OUT_P4") (pintype "bidirectional"))
      (node (ref "IC6") (pin "5") (pinfunction "P$5_5") (pintype "bidirectional"))
      (node (ref "IC9") (pin "1") (pinfunction "IN_1") (pintype "bidirectional"))
      (node (ref "IC9") (pin "3") (pinfunction "EN_3") (pintype "bidirectional"))
      (node (ref "J1") (pin "1") (pinfunction "S_1") (pintype "passive"))
      (node (ref "J2") (pin "4") (pinfunction "4_4") (pintype "passive"))
      (node (ref "J3") (pin "4") (pinfunction "4_4") (pintype "passive"))
      (node (ref "J4") (pin "4") (pinfunction "4_4") (pintype "passive"))
      (node (ref "L3") (pin "1") (pinfunction "1_1") (pintype "passive"))
      (node (ref "L4") (pin "1") (pinfunction "1_1") (pintype "passive"))
      (node (ref "Q11") (pin "3") (pinfunction "S_3") (pintype "passive"))
      (node (ref "Q12") (pin "3") (pinfunction "S_3") (pintype "passive"))
      (node (ref "Q7") (pin "3") (pinfunction "S_3") (pintype "passive"))
      (node (ref "Q8") (pin "3") (pinfunction "S_3") (pintype "passive"))
      (node (ref "R23") (pin "1") (pinfunction "1_1") (pintype "passive"))
      (node (ref "R24") (pin "1") (pinfunction "1_1") (pintype "passive"))
      (node (ref "R29") (pin "1") (pinfunction "1_1") (pintype "passive"))
      (node (ref "R30") (pin "1") (pinfunction "1_1") (pintype "passive"))
      (node (ref "R36") (pin "1") (pinfunction "1_1") (pintype "passive"))
      (node (ref "R37") (pin "1") (pinfunction "1_1") (pintype "passive"))
      (node (ref "R38") (pin "1") (pinfunction "1_1") (pintype "passive"))
      (node (ref "R5") (pin "2") (pinfunction "2_2") (pintype "passive"))
      (node (ref "X5") (pin "P1") (pinfunction "1_P1") (pintype "passive"))
    )
    (net (code "2") (name "+12V") (class "Default")
      (node (ref "C1") (pin "1") (pinfunction "1_1") (pintype "passive"))
      (node (ref "C2") (pin "+") (pinfunction "+_+") (pintype "passive"))
      (node (ref "D1") (pin "C") (pinfunction "C_C") (pintype "passive"))
      (node (ref "D2") (pin "C") (pinfunction "C_C") (pintype "passive"))
      (node (ref "D3") (pin "C") (pinfunction "C_C") (pintype "passive"))
      (node (ref "J2") (pin "6") (pinfunction "6_6") (pintype "passive"))
      (node (ref "J3") (pin "6") (pinfunction "6_6") (pintype "passive"))
      (node (ref "J4") (pin "6") (pinfunction "6_6") (pintype "passive"))
      (node (ref "JACK") (pin "P1") (pinfunction "1_P1") (pintype "passive"))
      (node (ref "L1") (pin "1") (pinfunction "1_1") (pintype "passive"))
    )
    (net (code "3") (name "5V_RAW") (class "Default")
      (node (ref "C10") (pin "1") (pinfunction "1_1") (pintype "passive"))
      (node (ref "C11") (pin "1") (pinfunction "1_1") (pintype "passive"))
      (node (ref "C12") (pin "+") (pinfunction "+_+") (pintype "passive"))
      (node (ref "IC3") (pin "1") (pinfunction "IN_1") (pintype "bidirectional"))
      (node (ref "IC3") (pin "3") (pinfunction "EN_3") (pintype "bidirectional"))
      (node (ref "IC4") (pin "20") (pinfunction "VCC_20") (pintype "power_in"))
      (node (ref "L2") (pin "1") (pinfunction "1_1") (pintype "passive"))
      (node (ref "R3") (pin "2") (pinfunction "2_2") (pintype "passive"))
      (node (ref "R4") (pin "2") (pinfunction "2_2") (pintype "passive"))
    )
    (net (code "4") (name "ADC0") (class "Default")
      (node (ref "C42") (pin "2") (pinfunction "2_2") (pintype "passive"))
      (node (ref "IC7") (pin "95") (pinfunction "PA0(ADCA0/AREFA)_95") (pintype "bidirectional"))
      (node (ref "R18") (pin "2") (pinfunction "2_2") (pintype "passive"))
    )
    (net (code "5") (name "ADC0_IN") (class "Default")
      (node (ref "R13") (pin "2") (pinfunction "2_2") (pintype "passive"))
      (node (ref "X5") (pin "P3") (pinfunction "3_P3") (pintype "passive"))
    )
    (net (code "6") (name "ADC1") (class "Default")
      (node (ref "C51") (pin "2") (pinfunction "2_2") (pintype "passive"))
      (node (ref "IC7") (pin "97") (pinfunction "PA2(ADCA2)_97") (pintype "bidirectional"))
      (node (ref "R49") (pin "2") (pinfunction "2_2") (pintype "passive"))
    )
    (net (code "7") (name "ADC1_IN") (class "Default")
      (node (ref "R50") (pin "2") (pinfunction "2_2") (pintype "passive"))
      (node (ref "X3") (pin "P1") (pinfunction "1_P1") (pintype "passive"))
    )
    (net (code "8") (name "CLK_IN") (class "Default")
      (node (ref "CLKIN") (pin "4") (pinfunction "4_4") (pintype "passive"))
      (node (ref "IC7") (pin "21") (pinfunction "PC6(MISO/RXD1)_21") (pintype "bidirectional"))
    )
    (net (code "9") (name "C_M0") (class "Default")
      (node (ref "IC8") (pin "2") (pinfunction "IN-_2") (pintype "input"))
      (node (ref "Q2") (pin "3") (pinfunction "S_3") (pintype "passive"))
      (node (ref "RI1") (pin "2") (pinfunction "2_2") (pintype "passive"))
    )
    (net (code "10") (name "C_M1") (class "Default")
      (node (ref "IC11") (pin "2") (pinfunction "IN-_2") (pintype "input"))
      (node (ref "Q4") (pin "3") (pinfunction "S_3") (pintype "passive"))
      (node (ref "RI3") (pin "2") (pinfunction "2_2") (pintype "passive"))
    )
    (net (code "11") (name "DAC0") (class "Default")
      (node (ref "IC7") (pin "8") (pinfunction "PB3(ADCB3/DAC1)_8") (pintype "bidirectional"))
      (node (ref "R15") (pin "1") (pinfunction "1_1") (pintype "passive"))
    )
    (net (code "12") (name "DAC1") (class "Default")
      (node (ref "IC7") (pin "7") (pinfunction "PB2(ADCB2/DAC0)_7") (pintype "bidirectional"))
      (node (ref "R9") (pin "1") (pinfunction "1_1") (pintype "passive"))
    )
    (net (code "13") (name "DI3") (class "Default")
      (node (ref "IC19") (pin "2") (pinfunction "P$2_2") (pintype "bidirectional"))
      (node (ref "R52") (pin "1") (pinfunction "1_1") (pintype "passive"))
      (node (ref "X3") (pin "P3") (pinfunction "3_P3") (pintype "passive"))
    )
    (net (code "14") (name "DIO_PK0") (class "Default")
      (node (ref "J2") (pin "2") (pinfunction "2_2") (pintype "passive"))
      (node (ref "Q15") (pin "3") (pinfunction "D_3") (pintype "passive"))
      (node (ref "R36") (pin "2") (pinfunction "2_2") (pintype "passive"))
    )
    (net (code "15") (name "DIO_PK1") (class "Default")
      (node (ref "J3") (pin "2") (pinfunction "2_2") (pintype "passive"))
      (node (ref "Q13") (pin "3") (pinfunction "D_3") (pintype "passive"))
      (node (ref "R37") (pin "2") (pinfunction "2_2") (pintype "passive"))
    )
    (net (code "16") (name "DIO_PK2") (class "Default")
      (node (ref "J4") (pin "2") (pinfunction "2_2") (pintype "passive"))
      (node (ref "Q14") (pin "3") (pinfunction "D_3") (pintype "passive"))
      (node (ref "R38") (pin "2") (pinfunction "2_2") (pintype "passive"))
    )
    (net (code "17") (name "DI_PK0") (class "Default")
      (node (ref "IC12") (pin "2") (pinfunction "P$2_2") (pintype "bidirectional"))
      (node (ref "J2") (pin "1") (pinfunction "1_1") (pintype "passive"))
      (node (ref "R39") (pin "1") (pinfunction "1_1") (pintype "passive"))
    )
    (net (code "18") (name "DI_PK1") (class "Default")
      (node (ref "IC14") (pin "2") (pinfunction "P$2_2") (pintype "bidirectional"))
      (node (ref "J3") (pin "1") (pinfunction "1_1") (pintype "passive"))
      (node (ref "R41") (pin "1") (pinfunction "1_1") (pintype "passive"))
    )
    (net (code "19") (name "DI_PK2") (class "Default")
      (node (ref "IC16") (pin "2") (pinfunction "P$2_2") (pintype "bidirectional"))
      (node (ref "J4") (pin "1") (pinfunction "1_1") (pintype "passive"))
      (node (ref "R43") (pin "1") (pinfunction "1_1") (pintype "passive"))
    )
    (net (code "20") (name "DO0") (class "Default")
      (node (ref "Q12") (pin "2") (pinfunction "D_2") (pintype "passive"))
      (node (ref "Q12") (pin "4") (pinfunction "D_4") (pintype "passive"))
      (node (ref "R32") (pin "2") (pinfunction "2_2") (pintype "passive"))
      (node (ref "X4") (pin "P5") (pinfunction "5_P5") (pintype "passive"))
    )
    (net (code "21") (name "DO1") (class "Default")
      (node (ref "Q8") (pin "2") (pinfunction "D_2") (pintype "passive"))
      (node (ref "Q8") (pin "4") (pinfunction "D_4") (pintype "passive"))
      (node (ref "R26") (pin "2") (pinfunction "2_2") (pintype "passive"))
      (node (ref "X4") (pin "P4") (pinfunction "4_P4") (pintype "passive"))
    )
    (net (code "22") (name "DO2") (class "Default")
      (node (ref "Q11") (pin "2") (pinfunction "D_2") (pintype "passive"))
      (node (ref "Q11") (pin "4") (pinfunction "D_4") (pintype "passive"))
      (node (ref "R31") (pin "2") (pinfunction "2_2") (pintype "passive"))
      (node (ref "X4") (pin "P2") (pinfunction "2_P2") (pintype "passive"))
    )
    (net (code "23") (name "DO3") (class "Default")
      (node (ref "Q7") (pin "2") (pinfunction "D_2") (pintype "passive"))
      (node (ref "Q7") (pin "4") (pinfunction "D_4") (pintype "passive"))
      (node (ref "R25") (pin "2") (pinfunction "2_2") (pintype "passive"))
      (node (ref "X4") (pin "P1") (pinfunction "1_P1") (pintype "passive"))
    )
    (net (code "24") (name "DO_PK0") (class "Default")
      (node (ref "IC13") (pin "4") (pinfunction "P$4_4") (pintype "bidirectional"))
      (node (ref "J2") (pin "3") (pinfunction "3_3") (pintype "passive"))
    )
    (net (code "25") (name "DO_PK1") (class "Default")
      (node (ref "IC15") (pin "4") (pinfunction "P$4_4") (pintype "bidirectional"))
      (node (ref "J3") (pin "3") (pinfunction "3_3") (pintype "passive"))
    )
    (net (code "26") (name "DO_PK2") (class "Default")
      (node (ref "IC17") (pin "4") (pinfunction "P$4_4") (pintype "bidirectional"))
      (node (ref "J4") (pin "3") (pinfunction "3_3") (pintype "passive"))
    )
    (net (code "27") (name "FT_CTS") (class "Default")
      (node (ref "IC4") (pin "11") (pinfunction "~{CTS}_11") (pintype "input"))
      (node (ref "IC7") (pin "75") (pinfunction "PK0(A0/A8/A16)_75") (pintype "bidirectional"))
    )
    (net (code "28") (name "FT_RTS") (class "Default")
      (node (ref "IC4") (pin "3") (pinfunction "~{RTS}_3") (pintype "output"))
      (node (ref "IC7") (pin "71") (pinfunction "PJ6(A10/D6/A6/A14)_71") (pintype "bidirectional"))
    )
    (net (code "29") (name "FT_RXD") (class "Default")
      (node (ref "IC4") (pin "5") (pinfunction "RXD_5") (pintype "input"))
      (node (ref "IC7") (pin "48") (pinfunction "PF3(OC0D/TXD0)_48") (pintype "bidirectional"))
    )
    (net (code "30") (name "FT_TXD") (class "Default")
      (node (ref "IC4") (pin "1") (pinfunction "TXD_1") (pintype "output"))
      (node (ref "IC7") (pin "47") (pinfunction "PF2(OC0C/RXD0)_47") (pintype "bidirectional"))
    )
    (net (code "31") (name "GND") (class "Default")
      (node (ref "C1") (pin "2") (pinfunction "2_2") (pintype "passive"))
      (node (ref "C10") (pin "2") (pinfunction "2_2") (pintype "passive"))
      (node (ref "C11") (pin "2") (pinfunction "2_2") (pintype "passive"))
      (node (ref "C12") (pin "-") (pinfunction "-_-") (pintype "passive"))
      (node (ref "C13") (pin "2") (pinfunction "2_2") (pintype "passive"))
      (node (ref "C14") (pin "2") (pinfunction "2_2") (pintype "passive"))
      (node (ref "C15") (pin "2") (pinfunction "2_2") (pintype "passive"))
      (node (ref "C16") (pin "2") (pinfunction "2_2") (pintype "passive"))
      (node (ref "C18") (pin "2") (pinfunction "2_2") (pintype "passive"))
      (node (ref "C19") (pin "2") (pinfunction "2_2") (pintype "passive"))
      (node (ref "C2") (pin "-") (pinfunction "-_-") (pintype "passive"))
      (node (ref "C20") (pin "2") (pinfunction "2_2") (pintype "passive"))
      (node (ref "C21") (pin "2") (pinfunction "2_2") (pintype "passive"))
      (node (ref "C22") (pin "2") (pinfunction "2_2") (pintype "passive"))
      (node (ref "C23") (pin "2") (pinfunction "2_2") (pintype "passive"))
      (node (ref "C24") (pin "2") (pinfunction "2_2") (pintype "passive"))
      (node (ref "C25") (pin "2") (pinfunction "2_2") (pintype "passive"))
      (node (ref "C26") (pin "2") (pinfunction "2_2") (pintype "passive"))
      (node (ref "C27") (pin "2") (pinfunction "2_2") (pintype "passive"))
      (node (ref "C28") (pin "2") (pinfunction "2_2") (pintype "passive"))
      (node (ref "C29") (pin "2") (pinfunction "2_2") (pintype "passive"))
      (node (ref "C3") (pin "-") (pinfunction "-_-") (pintype "passive"))
      (node (ref "C30") (pin "2") (pinfunction "2_2") (pintype "passive"))
      (node (ref "C31") (pin "2") (pinfunction "2_2") (pintype "passive"))
      (node (ref "C32") (pin "2") (pinfunction "2_2") (pintype "passive"))
      (node (ref "C33") (pin "2") (pinfunction "2_2") (pintype "passive"))
      (node (ref "C34") (pin "2") (pinfunction "2_2") (pintype "passive"))
      (node (ref "C35") (pin "2") (pinfunction "2_2") (pintype "passive"))
      (node (ref "C36") (pin "2") (pinfunction "2_2") (pintype "passive"))
      (node (ref "C37") (pin "2") (pinfunction "2_2") (pintype "passive"))
      (node (ref "C38") (pin "2") (pinfunction "2_2") (pintype "passive"))
      (node (ref "C39") (pin "2") (pinfunction "2_2") (pintype "passive"))
      (node (ref "C4") (pin "2") (pinfunction "2_2") (pintype "passive"))
      (node (ref "C40") (pin "2") (pinfunction "2_2") (pintype "passive"))
      (node (ref "C41") (pin "1") (pinfunction "1_1") (pintype "passive"))
      (node (ref "C42") (pin "1") (pinfunction "1_1") (pintype "passive"))
      (node (ref "C43") (pin "2") (pinfunction "2_2") (pintype "passive"))
      (node (ref "C44") (pin "2") (pinfunction "2_2") (pintype "passive"))
      (node (ref "C45") (pin "2") (pinfunction "2_2") (pintype "passive"))
      (node (ref "C46") (pin "2") (pinfunction "2_2") (pintype "passive"))
      (node (ref "C47") (pin "2") (pinfunction "2_2") (pintype "passive"))
      (node (ref "C48") (pin "2") (pinfunction "2_2") (pintype "passive"))
      (node (ref "C49") (pin "2") (pinfunction "2_2") (pintype "passive"))
      (node (ref "C5") (pin "2") (pinfunction "2_2") (pintype "passive"))
      (node (ref "C50") (pin "1") (pinfunction "1_1") (pintype "passive"))
      (node (ref "C51") (pin "1") (pinfunction "1_1") (pintype "passive"))
      (node (ref "C52") (pin "2") (pinfunction "2_2") (pintype "passive"))
      (node (ref "C53") (pin "2") (pinfunction "2_2") (pintype "passive"))
      (node (ref "C6") (pin "2") (pinfunction "2_2") (pintype "passive"))
      (node (ref "C7") (pin "2") (pinfunction "2_2") (pintype "passive"))
      (node (ref "C8") (pin "2") (pinfunction "2_2") (pintype "passive"))
      (node (ref "C9") (pin "2") (pinfunction "2_2") (pintype "passive"))
      (node (ref "CLKIN") (pin "5") (pinfunction "5_5") (pintype "passive"))
      (node (ref "CUSB") (pin "2") (pinfunction "2_2") (pintype "passive"))
      (node (ref "IC1") (pin "P$2") (pinfunction "GND_P$2") (pintype "bidirectional"))
      (node (ref "IC10") (pin "2") (pinfunction "V-_2") (pintype "power_in"))
      (node (ref "IC11") (pin "4") (pinfunction "-VS_4") (pintype "input"))
      (node (ref "IC12") (pin "1") (pinfunction "P$1_1") (pintype "bidirectional"))
      (node (ref "IC12") (pin "3") (pinfunction "P$3_3") (pintype "bidirectional"))
      (node (ref "IC13") (pin "1") (pinfunction "P$1_1") (pintype "bidirectional"))
      (node (ref "IC13") (pin "3") (pinfunction "P$3_3") (pintype "bidirectional"))
      (node (ref "IC14") (pin "1") (pinfunction "P$1_1") (pintype "bidirectional"))
      (node (ref "IC14") (pin "3") (pinfunction "P$3_3") (pintype "bidirectional"))
      (node (ref "IC15") (pin "1") (pinfunction "P$1_1") (pintype "bidirectional"))
      (node (ref "IC15") (pin "3") (pinfunction "P$3_3") (pintype "bidirectional"))
      (node (ref "IC16") (pin "1") (pinfunction "P$1_1") (pintype "bidirectional"))
      (node (ref "IC16") (pin "3") (pinfunction "P$3_3") (pintype "bidirectional"))
      (node (ref "IC17") (pin "1") (pinfunction "P$1_1") (pintype "bidirectional"))
      (node (ref "IC17") (pin "3") (pinfunction "P$3_3") (pintype "bidirectional"))
      (node (ref "IC18") (pin "2") (pinfunction "V-_2") (pintype "power_in"))
      (node (ref "IC19") (pin "1") (pinfunction "P$1_1") (pintype "bidirectional"))
      (node (ref "IC19") (pin "3") (pinfunction "P$3_3") (pintype "bidirectional"))
      (node (ref "IC2") (pin "P3") (pinfunction "GND_P3") (pintype "passive"))
      (node (ref "IC3") (pin "2") (pinfunction "GND_2") (pintype "bidirectional"))
      (node (ref "IC4") (pin "18") (pinfunction "GND_18") (pintype "power_in"))
      (node (ref "IC4") (pin "21") (pinfunction "GND_21") (pintype "power_in"))
      (node (ref "IC4") (pin "25") (pinfunction "GND_25") (pintype "power_in"))
      (node (ref "IC4") (pin "26") (pinfunction "TEST_26") (pintype "input"))
      (node (ref "IC4") (pin "7") (pinfunction "GND_7") (pintype "power_in"))
      (node (ref "IC5") (pin "P6") (pinfunction "GND_P6") (pintype "bidirectional"))
      (node (ref "IC5") (pin "P9") (pinfunction "GND_T_P9") (pintype "bidirectional"))
      (node (ref "IC6") (pin "1") (pinfunction "P$1_1") (pintype "bidirectional"))
      (node (ref "IC6") (pin "3") (pinfunction "P$3_3") (pintype "bidirectional"))
      (node (ref "IC7") (pin "13") (pinfunction "GND_13") (pintype "power_in"))
      (node (ref "IC7") (pin "23") (pinfunction "GND_23") (pintype "power_in"))
      (node (ref "IC7") (pin "3") (pinfunction "GND_3") (pintype "power_in"))
      (node (ref "IC7") (pin "33") (pinfunction "GND_33") (pintype "power_in"))
      (node (ref "IC7") (pin "43") (pinfunction "GND_43") (pintype "power_in"))
      (node (ref "IC7") (pin "53") (pinfunction "GND_53") (pintype "power_in"))
      (node (ref "IC7") (pin "63") (pinfunction "GND_63") (pintype "power_in"))
      (node (ref "IC7") (pin "73") (pinfunction "GND_73") (pintype "power_in"))
      (node (ref "IC7") (pin "84") (pinfunction "GND_84") (pintype "power_in"))
      (node (ref "IC7") (pin "93") (pinfunction "GND_93") (pintype "power_in"))
      (node (ref "IC7") (pin "96") (pinfunction "PA1(ADCA1)_96") (pintype "bidirectional"))
      (node (ref "IC8") (pin "4") (pinfunction "-VS_4") (pintype "input"))
      (node (ref "IC9") (pin "2") (pinfunction "GND_2") (pintype "bidirectional"))
      (node (ref "J1") (pin "3") (pinfunction "S_3") (pintype "passive"))
      (node (ref "J2") (pin "5") (pinfunction "5_5") (pintype "passive"))
      (node (ref "J3") (pin "5") (pinfunction "5_5") (pintype "passive"))
      (node (ref "J4") (pin "5") (pinfunction "5_5") (pintype "passive"))
      (node (ref "JACK") (pin "P2") (pinfunction "2_P2") (pintype "passive"))
      (node (ref "JACK") (pin "P3") (pinfunction "3_P3") (pintype "passive"))
      (node (ref "OSC1") (pin "P$2") (pinfunction "GND_P$2") (pintype "passive"))
      (node (ref "PDI") (pin "6") (pinfunction "6_6") (pintype "passive"))
      (node (ref "Q1") (pin "2") (pinfunction "S_2") (pintype "passive"))
      (node (ref "Q10") (pin "E") (pinfunction "E_E") (pintype "passive"))
      (node (ref "Q16") (pin "3") (pinfunction "S_3") (pintype "passive"))
      (node (ref "Q17") (pin "3") (pinfunction "S_3") (pintype "passive"))
      (node (ref "Q18") (pin "3") (pinfunction "S_3") (pintype "passive"))
      (node (ref "Q3") (pin "2") (pinfunction "S_2") (pintype "passive"))
      (node (ref "Q5") (pin "E") (pinfunction "E_E") (pintype "passive"))
      (node (ref "Q6") (pin "E") (pinfunction "E_E") (pintype "passive"))
      (node (ref "Q9") (pin "E") (pinfunction "E_E") (pintype "passive"))
      (node (ref "R14") (pin "1") (pinfunction "1_1") (pintype "passive"))
      (node (ref "R25") (pin "1") (pinfunction "1_1") (pintype "passive"))
      (node (ref "R26") (pin "1") (pinfunction "1_1") (pintype "passive"))
      (node (ref "R31") (pin "1") (pinfunction "1_1") (pintype "passive"))
      (node (ref "R32") (pin "1") (pinfunction "1_1") (pintype "passive"))
      (node (ref "R39") (pin "2") (pinfunction "2_2") (pintype "passive"))
      (node (ref "R40") (pin "1") (pinfunction "1_1") (pintype "passive"))
      (node (ref "R41") (pin "2") (pinfunction "2_2") (pintype "passive"))
      (node (ref "R42") (pin "1") (pinfunction "1_1") (pintype "passive"))
      (node (ref "R43") (pin "2") (pinfunction "2_2") (pintype "passive"))
      (node (ref "R44") (pin "2") (pinfunction "2_2") (pintype "passive"))
      (node (ref "R51") (pin "1") (pinfunction "1_1") (pintype "passive"))
      (node (ref "R52") (pin "2") (pinfunction "2_2") (pintype "passive"))
      (node (ref "R6") (pin "1") (pinfunction "1_1") (pintype "passive"))
      (node (ref "RI2") (pin "1") (pinfunction "1_1") (pintype "passive"))
      (node (ref "RI4") (pin "1") (pinfunction "1_1") (pintype "passive"))
      (node (ref "RTRIM") (pin "1") (pinfunction "1_1") (pintype "passive"))
      (node (ref "RUSB") (pin "2") (pinfunction "2_2") (pintype "passive"))
      (node (ref "STATE") (pin "K") (pinfunction "K_K") (pintype "bidirectional"))
      (node (ref "USB") (pin "P$5") (pinfunction "5_P$5") (pintype "bidirectional"))
      (node (ref "X3") (pin "P2") (pinfunction "2_P2") (pintype "passive"))
      (node (ref "X4") (pin "P3") (pinfunction "3_P3") (pintype "passive"))
      (node (ref "X4") (pin "P6") (pinfunction "6_P6") (pintype "passive"))
      (node (ref "X5") (pin "P2") (pinfunction "2_P2") (pintype "passive"))
      (node (ref "X5") (pin "P4") (pinfunction "4_P4") (pintype "passive"))
    )
    (net (code "32") (name "IN03") (class "Default")
      (node (ref "IC19") (pin "4") (pinfunction "P$4_4") (pintype "bidirectional"))
      (node (ref "IC7") (pin "55") (pinfunction "PH0(~{WE})_55") (pintype "bidirectional"))
    )
    (net (code "33") (name "I_OFF_DAC0") (class "Default")
      (node (ref "IC7") (pin "11") (pinfunction "PB6(ADCB6/TCK)_11") (pintype "bidirectional"))
      (node (ref "R17") (pin "2") (pinfunction "2_2") (pintype "passive"))
      (node (ref "R20") (pin "1") (pinfunction "1_1") (pintype "passive"))
    )
    (net (code "34") (name "I_OFF_DAC1") (class "Default")
      (node (ref "IC7") (pin "10") (pinfunction "PB5(ADCB5/TDI)_10") (pintype "bidirectional"))
      (node (ref "R10") (pin "2") (pinfunction "2_2") (pintype "passive"))
      (node (ref "R11") (pin "1") (pinfunction "1_1") (pintype "passive"))
    )
    (net (code "35") (name "LED_5V_0") (class "Default")
      (node (ref "C35") (pin "1") (pinfunction "1_1") (pintype "passive"))
      (node (ref "IC8") (pin "7") (pinfunction "+VS_7") (pintype "input"))
      (node (ref "L3") (pin "2") (pinfunction "2_2") (pintype "passive"))
      (node (ref "X1") (pin "P1") (pinfunction "1_P1") (pintype "passive"))
    )
    (net (code "36") (name "LED_5V_1") (class "Default")
      (node (ref "C40") (pin "1") (pinfunction "1_1") (pintype "passive"))
      (node (ref "IC11") (pin "7") (pinfunction "+VS_7") (pintype "input"))
      (node (ref "L4") (pin "2") (pinfunction "2_2") (pintype "passive"))
      (node (ref "X2") (pin "P1") (pinfunction "1_P1") (pintype "passive"))
    )
    (net (code "37") (name "LED_DATA") (class "Default")
      (node (ref "IC6") (pin "2") (pinfunction "P$2_2") (pintype "bidirectional"))
      (node (ref "IC7") (pin "20") (pinfunction "PC5(OC1B/MOSI/XCK1)_20") (pintype "bidirectional"))
    )
    (net (code "38") (name "LED_RTN0") (class "Default")
      (node (ref "Q2") (pin "2") (pinfunction "D_2") (pintype "passive"))
      (node (ref "Q2") (pin "4") (pinfunction "D_4") (pintype "passive"))
      (node (ref "X1") (pin "P2") (pinfunction "2_P2") (pintype "passive"))
    )
    (net (code "39") (name "LED_RTN1") (class "Default")
      (node (ref "Q4") (pin "2") (pinfunction "D_2") (pintype "passive"))
      (node (ref "Q4") (pin "4") (pinfunction "D_4") (pintype "passive"))
      (node (ref "X2") (pin "P2") (pinfunction "2_P2") (pintype "passive"))
    )
    (net (code "40") (name "Net-(C3-Pad+)") (class "Default")
      (node (ref "C3") (pin "+") (pinfunction "+_+") (pintype "passive"))
      (node (ref "R1") (pin "1") (pinfunction "1_1") (pintype "passive"))
    )
    (net (code "41") (name "Net-(C41-Pad2)") (class "Default")
      (node (ref "C41") (pin "2") (pinfunction "2_2") (pintype "passive"))
      (node (ref "R16") (pin "2") (pinfunction "2_2") (pintype "passive"))
      (node (ref "R18") (pin "1") (pinfunction "1_1") (pintype "passive"))
    )
    (net (code "42") (name "Net-(C50-Pad2)") (class "Default")
      (node (ref "C50") (pin "2") (pinfunction "2_2") (pintype "passive"))
      (node (ref "R48") (pin "2") (pinfunction "2_2") (pintype "passive"))
      (node (ref "R49") (pin "1") (pinfunction "1_1") (pintype "passive"))
    )
    (net (code "43") (name "Net-(CTUNE-Pad1)") (class "Default")
      (node (ref "CTUNE") (pin "1") (pinfunction "1_1") (pintype "passive"))
      (node (ref "RTUNE") (pin "1") (pinfunction "1_1") (pintype "passive"))
    )
    (net (code "44") (name "Net-(IC1-VBUS)") (class "Default")
      (node (ref "C5") (pin "1") (pinfunction "1_1") (pintype "passive"))
      (node (ref "IC1") (pin "P$5") (pinfunction "VBUS_P$5") (pintype "bidirectional"))
      (node (ref "L2") (pin "2") (pinfunction "2_2") (pintype "passive"))
      (node (ref "USB") (pin "P$1") (pinfunction "1_P$1") (pintype "bidirectional"))
    )
    (net (code "45") (name "Net-(IC2-ON{slash}OFF)") (class "Default")
      (node (ref "IC2") (pin "P1") (pinfunction "ON/OFF_P1") (pintype "passive"))
      (node (ref "R2") (pin "1") (pinfunction "1_1") (pintype "passive"))
    )
    (net (code "46") (name "Net-(IC2-TRIM)") (class "Default")
      (node (ref "CTUNE") (pin "2") (pinfunction "2_2") (pintype "passive"))
      (node (ref "IC2") (pin "P5") (pinfunction "TRIM_P5") (pintype "passive"))
      (node (ref "RTRIM") (pin "2") (pinfunction "2_2") (pintype "passive"))
    )
    (net (code "47") (name "Net-(IC2-VIN)") (class "Default")
      (node (ref "C4") (pin "1") (pinfunction "1_1") (pintype "passive"))
      (node (ref "IC2") (pin "P2") (pinfunction "VIN_P2") (pintype "passive"))
      (node (ref "L1") (pin "2") (pinfunction "2_2") (pintype "passive"))
      (node (ref "R1") (pin "2") (pinfunction "2_2") (pintype "passive"))
      (node (ref "R2") (pin "2") (pinfunction "2_2") (pintype "passive"))
    )
    (net (code "48") (name "Net-(IC4-3V3OUT)") (class "Default")
      (node (ref "C13") (pin "1") (pinfunction "1_1") (pintype "passive"))
      (node (ref "IC4") (pin "17") (pinfunction "3V3OUT_17") (pintype "output"))
    )
    (net (code "49") (name "Net-(IC4-CBUS0)") (class "Default")
      (node (ref "IC4") (pin "23") (pinfunction "CBUS0_23") (pintype "bidirectional"))
      (node (ref "TX") (pin "K") (pinfunction "K_K") (pintype "bidirectional"))
    )
    (net (code "50") (name "Net-(IC4-CBUS1)") (class "Default")
      (node (ref "IC4") (pin "22") (pinfunction "CBUS1_22") (pintype "bidirectional"))
      (node (ref "RX") (pin "K") (pinfunction "K_K") (pintype "bidirectional"))
    )
    (net (code "51") (name "Net-(IC5-NR{slash}FB)") (class "Default")
      (node (ref "C17") (pin "2") (pinfunction "2_2") (pintype "passive"))
      (node (ref "IC5") (pin "P5") (pinfunction "NR/FB_P5") (pintype "bidirectional"))
      (node (ref "R5") (pin "1") (pinfunction "1_1") (pintype "passive"))
      (node (ref "R6") (pin "2") (pinfunction "2_2") (pintype "passive"))
    )
    (net (code "52") (name "Net-(IC6-P$4)") (class "Default")
      (node (ref "IC6") (pin "4") (pinfunction "P$4_4") (pintype "bidirectional"))
      (node (ref "R7") (pin "2") (pinfunction "2_2") (pintype "passive"))
    )
    (net (code "53") (name "Net-(IC7-PR1(XTAL1))") (class "Default")
      (node (ref "IC7") (pin "92") (pinfunction "PR1(XTAL1)_92") (pintype "bidirectional"))
      (node (ref "OSC1") (pin "P$3") (pinfunction "OUTPUT_P$3") (pintype "passive"))
    )
    (net (code "54") (name "Net-(IC8-IN+)") (class "Default")
      (node (ref "C34") (pin "1") (pinfunction "1_1") (pintype "passive"))
      (node (ref "IC8") (pin "3") (pinfunction "IN+_3") (pintype "input"))
      (node (ref "R9") (pin "2") (pinfunction "2_2") (pintype "passive"))
    )
    (net (code "55") (name "Net-(IC8-OUT)") (class "Default")
      (node (ref "IC8") (pin "6") (pinfunction "OUT_6") (pintype "output"))
      (node (ref "R12") (pin "1") (pinfunction "1_1") (pintype "passive"))
    )
    (net (code "56") (name "Net-(IC10-+IN)") (class "Default")
      (node (ref "IC10") (pin "3") (pinfunction "+IN_3") (pintype "input"))
      (node (ref "R13") (pin "1") (pinfunction "1_1") (pintype "passive"))
      (node (ref "R14") (pin "2") (pinfunction "2_2") (pintype "passive"))
    )
    (net (code "57") (name "Net-(IC10--IN)") (class "Default")
      (node (ref "IC10") (pin "1") (pinfunction "OUT_1") (pintype "output"))
      (node (ref "IC10") (pin "4") (pinfunction "-IN_4") (pintype "input"))
      (node (ref "R16") (pin "1") (pinfunction "1_1") (pintype "passive"))
    )
    (net (code "58") (name "Net-(IC11-IN+)") (class "Default")
      (node (ref "C38") (pin "1") (pinfunction "1_1") (pintype "passive"))
      (node (ref "IC11") (pin "3") (pinfunction "IN+_3") (pintype "input"))
      (node (ref "R15") (pin "2") (pinfunction "2_2") (pintype "passive"))
    )
    (net (code "59") (name "Net-(IC11-OUT)") (class "Default")
      (node (ref "IC11") (pin "6") (pinfunction "OUT_6") (pintype "output"))
      (node (ref "R19") (pin "1") (pinfunction "1_1") (pintype "passive"))
    )
    (net (code "60") (name "Net-(IC18-+IN)") (class "Default")
      (node (ref "IC18") (pin "3") (pinfunction "+IN_3") (pintype "input"))
      (node (ref "R50") (pin "1") (pinfunction "1_1") (pintype "passive"))
      (node (ref "R51") (pin "2") (pinfunction "2_2") (pintype "passive"))
    )
    (net (code "61") (name "Net-(IC18--IN)") (class "Default")
      (node (ref "IC18") (pin "1") (pinfunction "OUT_1") (pintype "output"))
      (node (ref "IC18") (pin "4") (pinfunction "-IN_4") (pintype "input"))
      (node (ref "R48") (pin "1") (pinfunction "1_1") (pintype "passive"))
    )
    (net (code "62") (name "Net-(Q1-D)") (class "Default")
      (node (ref "Q1") (pin "3") (pinfunction "D_3") (pintype "passive"))
      (node (ref "Q2") (pin "1") (pinfunction "G_1") (pintype "passive"))
      (node (ref "R12") (pin "2") (pinfunction "2_2") (pintype "passive"))
    )
    (net (code "63") (name "Net-(Q1-G)") (class "Default")
      (node (ref "C37") (pin "1") (pinfunction "1_1") (pintype "passive"))
      (node (ref "Q1") (pin "1") (pinfunction "G_1") (pintype "passive"))
      (node (ref "R11") (pin "2") (pinfunction "2_2") (pintype "passive"))
    )
    (net (code "64") (name "Net-(Q3-D)") (class "Default")
      (node (ref "Q3") (pin "3") (pinfunction "D_3") (pintype "passive"))
      (node (ref "Q4") (pin "1") (pinfunction "G_1") (pintype "passive"))
      (node (ref "R19") (pin "2") (pinfunction "2_2") (pintype "passive"))
    )
    (net (code "65") (name "Net-(Q3-G)") (class "Default")
      (node (ref "C43") (pin "1") (pinfunction "1_1") (pintype "passive"))
      (node (ref "Q3") (pin "1") (pinfunction "G_1") (pintype "passive"))
      (node (ref "R20") (pin "2") (pinfunction "2_2") (pintype "passive"))
    )
    (net (code "66") (name "Net-(Q5-PadB)") (class "Default")
      (node (ref "Q5") (pin "B") (pinfunction "B_B") (pintype "passive"))
      (node (ref "R21") (pin "2") (pinfunction "2_2") (pintype "passive"))
    )
    (net (code "67") (name "Net-(Q6-PadB)") (class "Default")
      (node (ref "Q6") (pin "B") (pinfunction "B_B") (pintype "passive"))
      (node (ref "R22") (pin "2") (pinfunction "2_2") (pintype "passive"))
    )
    (net (code "68") (name "Net-(Q7-G)") (class "Default")
      (node (ref "Q5") (pin "C") (pinfunction "C_C") (pintype "passive"))
      (node (ref "Q7") (pin "1") (pinfunction "G_1") (pintype "passive"))
      (node (ref "R23") (pin "2") (pinfunction "2_2") (pintype "passive"))
    )
    (net (code "69") (name "Net-(Q8-G)") (class "Default")
      (node (ref "Q6") (pin "C") (pinfunction "C_C") (pintype "passive"))
      (node (ref "Q8") (pin "1") (pinfunction "G_1") (pintype "passive"))
      (node (ref "R24") (pin "2") (pinfunction "2_2") (pintype "passive"))
    )
    (net (code "70") (name "Net-(Q9-PadB)") (class "Default")
      (node (ref "Q9") (pin "B") (pinfunction "B_B") (pintype "passive"))
      (node (ref "R27") (pin "2") (pinfunction "2_2") (pintype "passive"))
    )
    (net (code "71") (name "Net-(Q10-PadB)") (class "Default")
      (node (ref "Q10") (pin "B") (pinfunction "B_B") (pintype "passive"))
      (node (ref "R28") (pin "2") (pinfunction "2_2") (pintype "passive"))
    )
    (net (code "72") (name "Net-(Q11-G)") (class "Default")
      (node (ref "Q11") (pin "1") (pinfunction "G_1") (pintype "passive"))
      (node (ref "Q9") (pin "C") (pinfunction "C_C") (pintype "passive"))
      (node (ref "R29") (pin "2") (pinfunction "2_2") (pintype "passive"))
    )
    (net (code "73") (name "Net-(Q12-G)") (class "Default")
      (node (ref "Q10") (pin "C") (pinfunction "C_C") (pintype "passive"))
      (node (ref "Q12") (pin "1") (pinfunction "G_1") (pintype "passive"))
      (node (ref "R30") (pin "2") (pinfunction "2_2") (pintype "passive"))
    )
    (net (code "74") (name "Net-(Q16-G)") (class "Default")
      (node (ref "Q16") (pin "1") (pinfunction "G_1") (pintype "passive"))
      (node (ref "R45") (pin "2") (pinfunction "2_2") (pintype "passive"))
    )
    (net (code "75") (name "Net-(Q17-G)") (class "Default")
      (node (ref "Q17") (pin "1") (pinfunction "G_1") (pintype "passive"))
      (node (ref "R46") (pin "2") (pinfunction "2_2") (pintype "passive"))
    )
    (net (code "76") (name "Net-(Q18-G)") (class "Default")
      (node (ref "Q18") (pin "1") (pinfunction "G_1") (pintype "passive"))
      (node (ref "R47") (pin "2") (pinfunction "2_2") (pintype "passive"))
    )
    (net (code "77") (name "Net-(R3-Pad1)") (class "Default")
      (node (ref "R3") (pin "1") (pinfunction "1_1") (pintype "passive"))
      (node (ref "TX") (pin "A") (pinfunction "A_A") (pintype "bidirectional"))
    )
    (net (code "78") (name "Net-(R4-Pad1)") (class "Default")
      (node (ref "R4") (pin "1") (pinfunction "1_1") (pintype "passive"))
      (node (ref "RX") (pin "A") (pinfunction "A_A") (pintype "bidirectional"))
    )
    (net (code "79") (name "Net-(R8-Pad1)") (class "Default")
      (node (ref "R8") (pin "1") (pinfunction "1_1") (pintype "passive"))
      (node (ref "STATE") (pin "A") (pinfunction "A_A") (pintype "bidirectional"))
    )
    (net (code "80") (name "Net-(RI1-Pad1)") (class "Default")
      (node (ref "RI1") (pin "1") (pinfunction "1_1") (pintype "passive"))
      (node (ref "RI2") (pin "2") (pinfunction "2_2") (pintype "passive"))
    )
    (net (code "81") (name "Net-(RI3-Pad1)") (class "Default")
      (node (ref "RI3") (pin "1") (pinfunction "1_1") (pintype "passive"))
      (node (ref "RI4") (pin "2") (pinfunction "2_2") (pintype "passive"))
    )
    (net (code "82") (name "Net-(USB-2)") (class "Default")
      (node (ref "IC1") (pin "P$1") (pinfunction "IO1_P$1") (pintype "bidirectional"))
      (node (ref "USB") (pin "P$2") (pinfunction "2_P$2") (pintype "bidirectional"))
    )
    (net (code "83") (name "Net-(USB-3)") (class "Default")
      (node (ref "IC1") (pin "P$3") (pinfunction "IO2_P$3") (pintype "bidirectional"))
      (node (ref "USB") (pin "P$3") (pinfunction "3_P$3") (pintype "bidirectional"))
    )
    (net (code "84") (name "Net-(USB-P$1)") (class "Default")
      (node (ref "RUSB") (pin "1") (pinfunction "1_1") (pintype "passive"))
      (node (ref "USB") (pin "SHIELD_1") (pinfunction "P$1_SHIELD_1") (pintype "bidirectional"))
    )
    (net (code "85") (name "Net-(USB-P$4)") (class "Default")
      (node (ref "CUSB") (pin "1") (pinfunction "1_1") (pintype "passive"))
      (node (ref "USB") (pin "SHIELD_4") (pinfunction "P$4_SHIELD_4") (pintype "bidirectional"))
    )
    (net (code "86") (name "P5.45V") (class "Default")
      (node (ref "C14") (pin "1") (pinfunction "1_1") (pintype "passive"))
      (node (ref "C8") (pin "1") (pinfunction "1_1") (pintype "passive"))
      (node (ref "C9") (pin "1") (pinfunction "1_1") (pintype "passive"))
      (node (ref "IC2") (pin "P4") (pinfunction "VOUT_P4") (pintype "passive"))
      (node (ref "IC5") (pin "P1") (pinfunction "IN_P1") (pintype "bidirectional"))
      (node (ref "IC5") (pin "P2") (pinfunction "IN_P2") (pintype "bidirectional"))
      (node (ref "IC5") (pin "P8") (pinfunction "EN_P8") (pintype "bidirectional"))
      (node (ref "RTUNE") (pin "2") (pinfunction "2_2") (pintype "passive"))
    )
    (net (code "87") (name "PDI-CLK") (class "Default")
      (node (ref "IC7") (pin "90") (pinfunction "PDI-CLK/~{RESET}_90") (pintype "input"))
      (node (ref "PDI") (pin "5") (pinfunction "5_5") (pintype "passive"))
    )
    (net (code "88") (name "PDI-DATA") (class "Default")
      (node (ref "IC7") (pin "89") (pinfunction "PDI-DATA_89") (pintype "bidirectional"))
      (node (ref "PDI") (pin "1") (pinfunction "1_1") (pintype "passive"))
    )
    (net (code "89") (name "PK0_IN") (class "Default")
      (node (ref "IC12") (pin "4") (pinfunction "P$4_4") (pintype "bidirectional"))
      (node (ref "IC7") (pin "29") (pinfunction "PD4(OC1A/~{SS})_29") (pintype "bidirectional"))
    )
    (net (code "90") (name "PK0_IO") (class "Default")
      (node (ref "IC7") (pin "30") (pinfunction "PD5(OC1B/XCK1/MOSI)_30") (pintype "bidirectional"))
      (node (ref "Q15") (pin "2") (pinfunction "S_2") (pintype "passive"))
      (node (ref "R35") (pin "2") (pinfunction "2_2") (pintype "passive"))
    )
    (net (code "91") (name "PK0_OUT") (class "Default")
      (node (ref "IC13") (pin "2") (pinfunction "P$2_2") (pintype "bidirectional"))
      (node (ref "IC7") (pin "31") (pinfunction "PD6(RXD1/MISO)_31") (pintype "bidirectional"))
      (node (ref "R40") (pin "2") (pinfunction "2_2") (pintype "passive"))
    )
    (net (code "92") (name "PK0_VAL") (class "Default")
      (node (ref "IC7") (pin "32") (pinfunction "PD7(TXD1/SCK/CLKO/EVO)_32") (pintype "bidirectional"))
      (node (ref "R45") (pin "1") (pinfunction "1_1") (pintype "passive"))
    )
    (net (code "93") (name "PK1_IN") (class "Default")
      (node (ref "IC14") (pin "4") (pinfunction "P$4_4") (pintype "bidirectional"))
      (node (ref "IC7") (pin "39") (pinfunction "PE4(OC1A/~{SS})_39") (pintype "bidirectional"))
    )
    (net (code "94") (name "PK1_IO") (class "Default")
      (node (ref "IC7") (pin "40") (pinfunction "PE5(OC1B/XCK1/MOSI)_40") (pintype "bidirectional"))
      (node (ref "Q13") (pin "2") (pinfunction "S_2") (pintype "passive"))
      (node (ref "R33") (pin "2") (pinfunction "2_2") (pintype "passive"))
    )
    (net (code "95") (name "PK1_OUT") (class "Default")
      (node (ref "IC15") (pin "2") (pinfunction "P$2_2") (pintype "bidirectional"))
      (node (ref "IC7") (pin "41") (pinfunction "PE6(RSC1/MISO/TOSC2)_41") (pintype "bidirectional"))
      (node (ref "R42") (pin "2") (pinfunction "2_2") (pintype "passive"))
    )
    (net (code "96") (name "PK1_VAL") (class "Default")
      (node (ref "IC7") (pin "42") (pinfunction "PE7(TSD1/SCK/CLKO/EVO/TOSC1)_42") (pintype "bidirectional"))
      (node (ref "R46") (pin "1") (pinfunction "1_1") (pintype "passive"))
    )
    (net (code "97") (name "PK2_IN") (class "Default")
      (node (ref "IC16") (pin "4") (pinfunction "P$4_4") (pintype "bidirectional"))
      (node (ref "IC7") (pin "49") (pinfunction "PF4(OC1A/~{SS})_49") (pintype "bidirectional"))
    )
    (net (code "98") (name "PK2_IO") (class "Default")
      (node (ref "IC7") (pin "50") (pinfunction "PF5(OC1B/XCK1/MOSI)_50") (pintype "bidirectional"))
      (node (ref "Q14") (pin "2") (pinfunction "S_2") (pintype "passive"))
      (node (ref "R34") (pin "2") (pinfunction "2_2") (pintype "passive"))
    )
    (net (code "99") (name "PK2_OUT") (class "Default")
      (node (ref "IC17") (pin "2") (pinfunction "P$2_2") (pintype "bidirectional"))
      (node (ref "IC7") (pin "51") (pinfunction "PF6(RXD1/MISO)_51") (pintype "bidirectional"))
      (node (ref "R44") (pin "1") (pinfunction "1_1") (pintype "passive"))
    )
    (net (code "100") (name "PK2_VAL") (class "Default")
      (node (ref "IC7") (pin "52") (pinfunction "PF7(TXD1/SCK)_52") (pintype "bidirectional"))
      (node (ref "R47") (pin "1") (pinfunction "1_1") (pintype "passive"))
    )
    (net (code "101") (name "SERIAL_LED0") (class "Default")
      (node (ref "J1") (pin "2") (pinfunction "S_2") (pintype "passive"))
      (node (ref "R7") (pin "1") (pinfunction "1_1") (pintype "passive"))
    )
    (net (code "102") (name "STATE") (class "Default")
      (node (ref "IC7") (pin "1") (pinfunction "PA6(ADCA6)_1") (pintype "bidirectional"))
      (node (ref "R8") (pin "2") (pinfunction "2_2") (pintype "passive"))
    )
    (net (code "103") (name "TOG_D00") (class "Default")
      (node (ref "IC7") (pin "45") (pinfunction "PF0(OC0A/SDA)_45") (pintype "bidirectional"))
      (node (ref "R28") (pin "1") (pinfunction "1_1") (pintype "passive"))
    )
    (net (code "104") (name "TOG_D01") (class "Default")
      (node (ref "IC7") (pin "35") (pinfunction "PE0(OC0A/SDA)_35") (pintype "bidirectional"))
      (node (ref "R22") (pin "1") (pinfunction "1_1") (pintype "passive"))
    )
    (net (code "105") (name "TOG_D02") (class "Default")
      (node (ref "IC7") (pin "25") (pinfunction "PD0(OC0A/SDA)_25") (pintype "bidirectional"))
      (node (ref "R27") (pin "1") (pinfunction "1_1") (pintype "passive"))
    )
    (net (code "106") (name "TOG_D03") (class "Default")
      (node (ref "IC7") (pin "15") (pinfunction "PC0(OC0A/SDA)_15") (pintype "bidirectional"))
      (node (ref "R21") (pin "1") (pinfunction "1_1") (pintype "passive"))
    )
    (net (code "107") (name "USBDM") (class "Default")
      (node (ref "C7") (pin "1") (pinfunction "1_1") (pintype "passive"))
      (node (ref "IC1") (pin "P$6") (pinfunction "IO1_P$6") (pintype "bidirectional"))
      (node (ref "IC4") (pin "16") (pinfunction "USBDM_16") (pintype "bidirectional"))
    )
    (net (code "108") (name "USBDP") (class "Default")
      (node (ref "C6") (pin "1") (pinfunction "1_1") (pintype "passive"))
      (node (ref "IC1") (pin "P$4") (pinfunction "IO2_P$4") (pintype "bidirectional"))
      (node (ref "IC4") (pin "15") (pinfunction "USBDP_15") (pintype "bidirectional"))
    )
    (net (code "109") (name "VAL_PK0") (class "Default")
      (node (ref "D1") (pin "A") (pinfunction "A_A") (pintype "passive"))
      (node (ref "J2") (pin "7") (pinfunction "7_7") (pintype "passive"))
      (node (ref "Q16") (pin "2") (pinfunction "D_2") (pintype "passive"))
      (node (ref "Q16") (pin "4") (pinfunction "D_4") (pintype "passive"))
    )
    (net (code "110") (name "VAL_PK1") (class "Default")
      (node (ref "D2") (pin "A") (pinfunction "A_A") (pintype "passive"))
      (node (ref "J3") (pin "7") (pinfunction "7_7") (pintype "passive"))
      (node (ref "Q17") (pin "2") (pinfunction "D_2") (pintype "passive"))
      (node (ref "Q17") (pin "4") (pinfunction "D_4") (pintype "passive"))
    )
    (net (code "111") (name "VAL_PK2") (class "Default")
      (node (ref "D3") (pin "A") (pinfunction "A_A") (pintype "passive"))
      (node (ref "J4") (pin "7") (pinfunction "7_7") (pintype "passive"))
      (node (ref "Q18") (pin "2") (pinfunction "D_2") (pintype "passive"))
      (node (ref "Q18") (pin "4") (pinfunction "D_4") (pintype "passive"))
    )
    (net (code "112") (name "VCCIO") (class "Default")
      (node (ref "C15") (pin "1") (pinfunction "1_1") (pintype "passive"))
      (node (ref "C16") (pin "1") (pinfunction "1_1") (pintype "passive"))
      (node (ref "C20") (pin "1") (pinfunction "1_1") (pintype "passive"))
      (node (ref "C21") (pin "1") (pinfunction "1_1") (pintype "passive"))
      (node (ref "C22") (pin "1") (pinfunction "1_1") (pintype "passive"))
      (node (ref "C23") (pin "1") (pinfunction "1_1") (pintype "passive"))
      (node (ref "C24") (pin "1") (pinfunction "1_1") (pintype "passive"))
      (node (ref "C26") (pin "1") (pinfunction "1_1") (pintype "passive"))
      (node (ref "C28") (pin "1") (pinfunction "1_1") (pintype "passive"))
      (node (ref "C30") (pin "1") (pinfunction "1_1") (pintype "passive"))
      (node (ref "C31") (pin "1") (pinfunction "1_1") (pintype "passive"))
      (node (ref "C32") (pin "1") (pinfunction "1_1") (pintype "passive"))
      (node (ref "C44") (pin "1") (pinfunction "1_1") (pintype "passive"))
      (node (ref "C46") (pin "1") (pinfunction "1_1") (pintype "passive"))
      (node (ref "C48") (pin "1") (pinfunction "1_1") (pintype "passive"))
      (node (ref "C53") (pin "1") (pinfunction "1_1") (pintype "passive"))
      (node (ref "CLKIN") (pin "1") (pinfunction "1_1") (pintype "passive"))
      (node (ref "D4") (pin "A") (pinfunction "A_A") (pintype "passive"))
      (node (ref "IC12") (pin "5") (pinfunction "P$5_5") (pintype "bidirectional"))
      (node (ref "IC14") (pin "5") (pinfunction "P$5_5") (pintype "bidirectional"))
      (node (ref "IC16") (pin "5") (pinfunction "P$5_5") (pintype "bidirectional"))
      (node (ref "IC19") (pin "5") (pinfunction "P$5_5") (pintype "bidirectional"))
      (node (ref "IC3") (pin "5") (pinfunction "OUT_5") (pintype "bidirectional"))
      (node (ref "IC4") (pin "4") (pinfunction "VCCIO_4") (pintype "power_in"))
      (node (ref "IC7") (pin "14") (pinfunction "VCC_14") (pintype "power_in"))
      (node (ref "IC7") (pin "24") (pinfunction "VCC_24") (pintype "power_in"))
      (node (ref "IC7") (pin "34") (pinfunction "VCC_34") (pintype "power_in"))
      (node (ref "IC7") (pin "44") (pinfunction "VCC_44") (pintype "power_in"))
      (node (ref "IC7") (pin "54") (pinfunction "VCC_54") (pintype "power_in"))
      (node (ref "IC7") (pin "64") (pinfunction "VCC_64") (pintype "power_in"))
      (node (ref "IC7") (pin "65") (pinfunction "PJ0(D0/A0/A8)_65") (pintype "bidirectional"))
      (node (ref "IC7") (pin "74") (pinfunction "VCC_74") (pintype "power_in"))
      (node (ref "IC7") (pin "83") (pinfunction "VCC_83") (pintype "power_in"))
      (node (ref "OSC1") (pin "P$4") (pinfunction "VDD_P$4") (pintype "passive"))
      (node (ref "PDI") (pin "2") (pinfunction "2_2") (pintype "passive"))
      (node (ref "Q13") (pin "1") (pinfunction "G_1") (pintype "passive"))
      (node (ref "Q14") (pin "1") (pinfunction "G_1") (pintype "passive"))
      (node (ref "Q15") (pin "1") (pinfunction "G_1") (pintype "passive"))
      (node (ref "R10") (pin "1") (pinfunction "1_1") (pintype "passive"))
      (node (ref "R17") (pin "1") (pinfunction "1_1") (pintype "passive"))
      (node (ref "R33") (pin "1") (pinfunction "1_1") (pintype "passive"))
      (node (ref "R34") (pin "1") (pinfunction "1_1") (pintype "passive"))
      (node (ref "R35") (pin "1") (pinfunction "1_1") (pintype "passive"))
    )
    (net (code "113") (name "VDD") (class "Default")
      (node (ref "C25") (pin "1") (pinfunction "1_1") (pintype "passive"))
      (node (ref "C27") (pin "1") (pinfunction "1_1") (pintype "passive"))
      (node (ref "C29") (pin "1") (pinfunction "1_1") (pintype "passive"))
      (node (ref "C36") (pin "1") (pinfunction "1_1") (pintype "passive"))
      (node (ref "C39") (pin "1") (pinfunction "1_1") (pintype "passive"))
      (node (ref "C52") (pin "1") (pinfunction "1_1") (pintype "passive"))
      (node (ref "D4") (pin "C") (pinfunction "C_C") (pintype "passive"))
      (node (ref "IC10") (pin "5") (pinfunction "V+_5") (pintype "power_in"))
      (node (ref "IC18") (pin "5") (pinfunction "V+_5") (pintype "power_in"))
      (node (ref "IC7") (pin "4") (pinfunction "AVCC-B_4") (pintype "power_in"))
      (node (ref "IC7") (pin "94") (pinfunction "AVCC-A_94") (pintype "power_in"))
      (node (ref "IC9") (pin "5") (pinfunction "OUT_5") (pintype "bidirectional"))
    )
    (net (code "114") (name "unconnected-(IC3-N{slash}C-Pad4)") (class "Default")
      (node (ref "IC3") (pin "4") (pinfunction "N/C_4") (pintype "bidirectional"))
    )
    (net (code "115") (name "unconnected-(IC4-CBUS2-Pad13)") (class "Default")
      (node (ref "IC4") (pin "13") (pinfunction "CBUS2_13") (pintype "bidirectional"))
    )
    (net (code "116") (name "unconnected-(IC4-CBUS3-Pad14)") (class "Default")
      (node (ref "IC4") (pin "14") (pinfunction "CBUS3_14") (pintype "bidirectional"))
    )
    (net (code "117") (name "unconnected-(IC4-CBUS4-Pad12)") (class "Default")
      (node (ref "IC4") (pin "12") (pinfunction "CBUS4_12") (pintype "bidirectional"))
    )
    (net (code "118") (name "unconnected-(IC4-OSCI-Pad27)") (class "Default")
      (node (ref "IC4") (pin "27") (pinfunction "OSCI_27") (pintype "input"))
    )
    (net (code "119") (name "unconnected-(IC4-OSCO-Pad28)") (class "Default")
      (node (ref "IC4") (pin "28") (pinfunction "OSCO_28") (pintype "output"))
    )
    (net (code "120") (name "unconnected-(IC4-~{DCD}-Pad10)") (class "Default")
      (node (ref "IC4") (pin "10") (pinfunction "~{DCD}_10") (pintype "input"))
    )
    (net (code "121") (name "unconnected-(IC4-~{DSR}-Pad9)") (class "Default")
      (node (ref "IC4") (pin "9") (pinfunction "~{DSR}_9") (pintype "input"))
    )
    (net (code "122") (name "unconnected-(IC4-~{DTR}-Pad2)") (class "Default")
      (node (ref "IC4") (pin "2") (pinfunction "~{DTR}_2") (pintype "output"))
    )
    (net (code "123") (name "unconnected-(IC4-~{RESET}-Pad19)") (class "Default")
      (node (ref "IC4") (pin "19") (pinfunction "~{RESET}_19") (pintype "input"))
    )
    (net (code "124") (name "unconnected-(IC4-~{RI}-Pad6)") (class "Default")
      (node (ref "IC4") (pin "6") (pinfunction "~{RI}_6") (pintype "input"))
    )
    (net (code "125") (name "unconnected-(IC7-PA3(ADCA3)-Pad98)") (class "Default")
      (node (ref "IC7") (pin "98") (pinfunction "PA3(ADCA3)_98") (pintype "bidirectional"))
    )
    (net (code "126") (name "unconnected-(IC7-PA4(ADCA4)-Pad99)") (class "Default")
      (node (ref "IC7") (pin "99") (pinfunction "PA4(ADCA4)_99") (pintype "bidirectional"))
    )
    (net (code "127") (name "unconnected-(IC7-PA5(ADCA5)-Pad100)") (class "Default")
      (node (ref "IC7") (pin "100") (pinfunction "PA5(ADCA5)_100") (pintype "bidirectional"))
    )
    (net (code "128") (name "unconnected-(IC7-PA7{slash}(ADCA7{slash}AC0-OUT)-Pad2)") (class "Default")
      (node (ref "IC7") (pin "2") (pinfunction "PA7/(ADCA7/AC0-OUT)_2") (pintype "bidirectional"))
    )
    (net (code "129") (name "unconnected-(IC7-PB0(ADCB0{slash}AREFB)-Pad5)") (class "Default")
      (node (ref "IC7") (pin "5") (pinfunction "PB0(ADCB0/AREFB)_5") (pintype "bidirectional"))
    )
    (net (code "130") (name "unconnected-(IC7-PB1(ADCB1)-Pad6)") (class "Default")
      (node (ref "IC7") (pin "6") (pinfunction "PB1(ADCB1)_6") (pintype "bidirectional"))
    )
    (net (code "131") (name "unconnected-(IC7-PB4(ADCB4{slash}TMS)-Pad9)") (class "Default")
      (node (ref "IC7") (pin "9") (pinfunction "PB4(ADCB4/TMS)_9") (pintype "bidirectional"))
    )
    (net (code "132") (name "unconnected-(IC7-PB7(ADCB7{slash}AC0-OUT{slash}TDO)-Pad12)") (class "Default")
      (node (ref "IC7") (pin "12") (pinfunction "PB7(ADCB7/AC0-OUT/TDO)_12") (pintype "bidirectional"))
    )
    (net (code "133") (name "unconnected-(IC7-PC1(OC0B{slash}XCK0{slash}SCL)-Pad16)") (class "Default")
      (node (ref "IC7") (pin "16") (pinfunction "PC1(OC0B/XCK0/SCL)_16") (pintype "bidirectional"))
    )
    (net (code "134") (name "unconnected-(IC7-PC2(OC0C{slash}RXD0)-Pad17)") (class "Default")
      (node (ref "IC7") (pin "17") (pinfunction "PC2(OC0C/RXD0)_17") (pintype "bidirectional"))
    )
    (net (code "135") (name "unconnected-(IC7-PC3(OC0D{slash}TXD0)-Pad18)") (class "Default")
      (node (ref "IC7") (pin "18") (pinfunction "PC3(OC0D/TXD0)_18") (pintype "bidirectional"))
    )
    (net (code "136") (name "unconnected-(IC7-PC4(OC1A{slash}~{SS})-Pad19)") (class "Default")
      (node (ref "IC7") (pin "19") (pinfunction "PC4(OC1A/~{SS})_19") (pintype "bidirectional"))
    )
    (net (code "137") (name "unconnected-(IC7-PC7(SCK{slash}TXD1{slash}CLKO{slash}EVO)-Pad22)") (class "Default")
      (node (ref "IC7") (pin "22") (pinfunction "PC7(SCK/TXD1/CLKO/EVO)_22") (pintype "bidirectional"))
    )
    (net (code "138") (name "unconnected-(IC7-PD1(OC0B{slash}XCK0{slash}SCL)-Pad26)") (class "Default")
      (node (ref "IC7") (pin "26") (pinfunction "PD1(OC0B/XCK0/SCL)_26") (pintype "bidirectional"))
    )
    (net (code "139") (name "unconnected-(IC7-PD2(OC0C{slash}RXD0)-Pad27)") (class "Default")
      (node (ref "IC7") (pin "27") (pinfunction "PD2(OC0C/RXD0)_27") (pintype "bidirectional"))
    )
    (net (code "140") (name "unconnected-(IC7-PD3(OC0D{slash}TXD0)-Pad28)") (class "Default")
      (node (ref "IC7") (pin "28") (pinfunction "PD3(OC0D/TXD0)_28") (pintype "bidirectional"))
    )
    (net (code "141") (name "unconnected-(IC7-PE1(OC0B{slash}XCK0{slash}SCL)-Pad36)") (class "Default")
      (node (ref "IC7") (pin "36") (pinfunction "PE1(OC0B/XCK0/SCL)_36") (pintype "bidirectional"))
    )
    (net (code "142") (name "unconnected-(IC7-PE2(OC0C{slash}RXD0)-Pad37)") (class "Default")
      (node (ref "IC7") (pin "37") (pinfunction "PE2(OC0C/RXD0)_37") (pintype "bidirectional"))
    )
    (net (code "143") (name "unconnected-(IC7-PE3(OC0D{slash}TXD0)-Pad38)") (class "Default")
      (node (ref "IC7") (pin "38") (pinfunction "PE3(OC0D/TXD0)_38") (pintype "bidirectional"))
    )
    (net (code "144") (name "unconnected-(IC7-PF1(OC0B{slash}XCK0{slash}SCL)-Pad46)") (class "Default")
      (node (ref "IC7") (pin "46") (pinfunction "PF1(OC0B/XCK0/SCL)_46") (pintype "bidirectional"))
    )
    (net (code "145") (name "unconnected-(IC7-PH1(~{CAS}{slash}~{RE})-Pad56)") (class "Default")
      (node (ref "IC7") (pin "56") (pinfunction "PH1(~{CAS}/~{RE})_56") (pintype "bidirectional"))
    )
    (net (code "146") (name "unconnected-(IC7-PH2(~{RAS}{slash}ALE1)-Pad57)") (class "Default")
      (node (ref "IC7") (pin "57") (pinfunction "PH2(~{RAS}/ALE1)_57") (pintype "bidirectional"))
    )
    (net (code "147") (name "unconnected-(IC7-PH3(~{DOM}{slash}ALE2)-Pad58)") (class "Default")
      (node (ref "IC7") (pin "58") (pinfunction "PH3(~{DOM}/ALE2)_58") (pintype "bidirectional"))
    )
    (net (code "148") (name "unconnected-(IC7-PH4(BA0{slash}~{CS0}{slash}A16)-Pad59)") (class "Default")
      (node (ref "IC7") (pin "59") (pinfunction "PH4(BA0/~{CS0}/A16)_59") (pintype "bidirectional"))
    )
    (net (code "149") (name "unconnected-(IC7-PH5(BA1{slash}~{CS1}{slash}A17)-Pad60)") (class "Default")
      (node (ref "IC7") (pin "60") (pinfunction "PH5(BA1/~{CS1}/A17)_60") (pintype "bidirectional"))
    )
    (net (code "150") (name "unconnected-(IC7-PH6(CKE{slash}~{CS2}{slash}A18)-Pad61)") (class "Default")
      (node (ref "IC7") (pin "61") (pinfunction "PH6(CKE/~{CS2}/A18)_61") (pintype "bidirectional"))
    )
    (net (code "151") (name "unconnected-(IC7-PH7(CLK{slash}~{CS3}{slash}A19)-Pad62)") (class "Default")
      (node (ref "IC7") (pin "62") (pinfunction "PH7(CLK/~{CS3}/A19)_62") (pintype "bidirectional"))
    )
    (net (code "152") (name "unconnected-(IC7-PJ1(D1{slash}A1{slash}A9)-Pad66)") (class "Default")
      (node (ref "IC7") (pin "66") (pinfunction "PJ1(D1/A1/A9)_66") (pintype "bidirectional"))
    )
    (net (code "153") (name "unconnected-(IC7-PJ2(D2{slash}A2{slash}A10)-Pad67)") (class "Default")
      (node (ref "IC7") (pin "67") (pinfunction "PJ2(D2/A2/A10)_67") (pintype "bidirectional"))
    )
    (net (code "154") (name "unconnected-(IC7-PJ3(D3{slash}A3{slash}A11)-Pad68)") (class "Default")
      (node (ref "IC7") (pin "68") (pinfunction "PJ3(D3/A3/A11)_68") (pintype "bidirectional"))
    )
    (net (code "155") (name "unconnected-(IC7-PJ4(A8{slash}D4{slash}A4{slash}A12)-Pad69)") (class "Default")
      (node (ref "IC7") (pin "69") (pinfunction "PJ4(A8/D4/A4/A12)_69") (pintype "bidirectional"))
    )
    (net (code "156") (name "unconnected-(IC7-PJ5(A9{slash}D5{slash}A5{slash}A13)-Pad70)") (class "Default")
      (node (ref "IC7") (pin "70") (pinfunction "PJ5(A9/D5/A5/A13)_70") (pintype "bidirectional"))
    )
    (net (code "157") (name "unconnected-(IC7-PJ7(A11{slash}D7{slash}A7{slash}A15)-Pad72)") (class "Default")
      (node (ref "IC7") (pin "72") (pinfunction "PJ7(A11/D7/A7/A15)_72") (pintype "bidirectional"))
    )
    (net (code "158") (name "unconnected-(IC7-PK1(A1{slash}A9{slash}A17)-Pad76)") (class "Default")
      (node (ref "IC7") (pin "76") (pinfunction "PK1(A1/A9/A17)_76") (pintype "bidirectional"))
    )
    (net (code "159") (name "unconnected-(IC7-PK2(A2{slash}A10{slash}A18)-Pad77)") (class "Default")
      (node (ref "IC7") (pin "77") (pinfunction "PK2(A2/A10/A18)_77") (pintype "bidirectional"))
    )
    (net (code "160") (name "unconnected-(IC7-PK3(A3{slash}A11{slash}A19)-Pad78)") (class "Default")
      (node (ref "IC7") (pin "78") (pinfunction "PK3(A3/A11/A19)_78") (pintype "bidirectional"))
    )
    (net (code "161") (name "unconnected-(IC7-PK4(A4{slash}A12{slash}A20)-Pad79)") (class "Default")
      (node (ref "IC7") (pin "79") (pinfunction "PK4(A4/A12/A20)_79") (pintype "bidirectional"))
    )
    (net (code "162") (name "unconnected-(IC7-PK5(A5{slash}A13{slash}A22)-Pad80)") (class "Default")
      (node (ref "IC7") (pin "80") (pinfunction "PK5(A5/A13/A22)_80") (pintype "bidirectional"))
    )
    (net (code "163") (name "unconnected-(IC7-PK6(A6{slash}A14{slash}A22)-Pad81)") (class "Default")
      (node (ref "IC7") (pin "81") (pinfunction "PK6(A6/A14/A22)_81") (pintype "bidirectional"))
    )
    (net (code "164") (name "unconnected-(IC7-PK7(A7{slash}A15{slash}A23)-Pad82)") (class "Default")
      (node (ref "IC7") (pin "82") (pinfunction "PK7(A7/A15/A23)_82") (pintype "bidirectional"))
    )
    (net (code "165") (name "unconnected-(IC7-PQ0(TOSC1)-Pad85)") (class "Default")
      (node (ref "IC7") (pin "85") (pinfunction "PQ0(TOSC1)_85") (pintype "bidirectional"))
    )
    (net (code "166") (name "unconnected-(IC7-PQ1(TOSC2)-Pad86)") (class "Default")
      (node (ref "IC7") (pin "86") (pinfunction "PQ1(TOSC2)_86") (pintype "bidirectional"))
    )
    (net (code "167") (name "unconnected-(IC7-PQ2-Pad87)") (class "Default")
      (node (ref "IC7") (pin "87") (pinfunction "PQ2_87") (pintype "bidirectional"))
    )
    (net (code "168") (name "unconnected-(IC7-PQ3-Pad88)") (class "Default")
      (node (ref "IC7") (pin "88") (pinfunction "PQ3_88") (pintype "bidirectional"))
    )
    (net (code "169") (name "unconnected-(IC7-PR0(XTAL2)-Pad91)") (class "Default")
      (node (ref "IC7") (pin "91") (pinfunction "PR0(XTAL2)_91") (pintype "bidirectional"))
    )
    (net (code "170") (name "unconnected-(IC8-DISABLE-Pad8)") (class "Default")
      (node (ref "IC8") (pin "8") (pinfunction "DISABLE_8") (pintype "passive"))
    )
    (net (code "171") (name "unconnected-(IC9-N{slash}C-Pad4)") (class "Default")
      (node (ref "IC9") (pin "4") (pinfunction "N/C_4") (pintype "bidirectional"))
    )
    (net (code "172") (name "unconnected-(IC11-DISABLE-Pad8)") (class "Default")
      (node (ref "IC11") (pin "8") (pinfunction "DISABLE_8") (pintype "passive"))
    )
    (net (code "173") (name "unconnected-(J2-Pad8)") (class "Default")
      (node (ref "J2") (pin "8") (pinfunction "8_8") (pintype "passive"))
    )
    (net (code "174") (name "unconnected-(J3-Pad8)") (class "Default")
      (node (ref "J3") (pin "8") (pinfunction "8_8") (pintype "passive"))
    )
    (net (code "175") (name "unconnected-(J4-Pad8)") (class "Default")
      (node (ref "J4") (pin "8") (pinfunction "8_8") (pintype "passive"))
    )
    (net (code "176") (name "unconnected-(OSC1-STANDBY#-PadP$1)") (class "Default")
      (node (ref "OSC1") (pin "P$1") (pinfunction "STANDBY#_P$1") (pintype "passive"))
    )
    (net (code "177") (name "unconnected-(PDI-Pad3)") (class "Default")
      (node (ref "PDI") (pin "3") (pinfunction "3_3") (pintype "passive"))
    )
    (net (code "178") (name "unconnected-(PDI-Pad4)") (class "Default")
      (node (ref "PDI") (pin "4") (pinfunction "4_4") (pintype "passive"))
    )
    (net (code "179") (name "unconnected-(USB-4-PadP$4)") (class "Default")
      (node (ref "USB") (pin "P$4") (pinfunction "4_P$4") (pintype "bidirectional"))
    )
    (net (code "180") (name "unconnected-(USB-P$2-PadSHIELD_2)") (class "Default")
      (node (ref "USB") (pin "SHIELD_2") (pinfunction "P$2_SHIELD_2") (pintype "bidirectional"))
    )
    (net (code "181") (name "unconnected-(USB-P$3-PadSHIELD_3)") (class "Default")
      (node (ref "USB") (pin "SHIELD_3") (pinfunction "P$3_SHIELD_3") (pintype "bidirectional"))
    )
  )
)
